# V4_0.net
KiCad netlist of a schematic drawn in Altium Designer
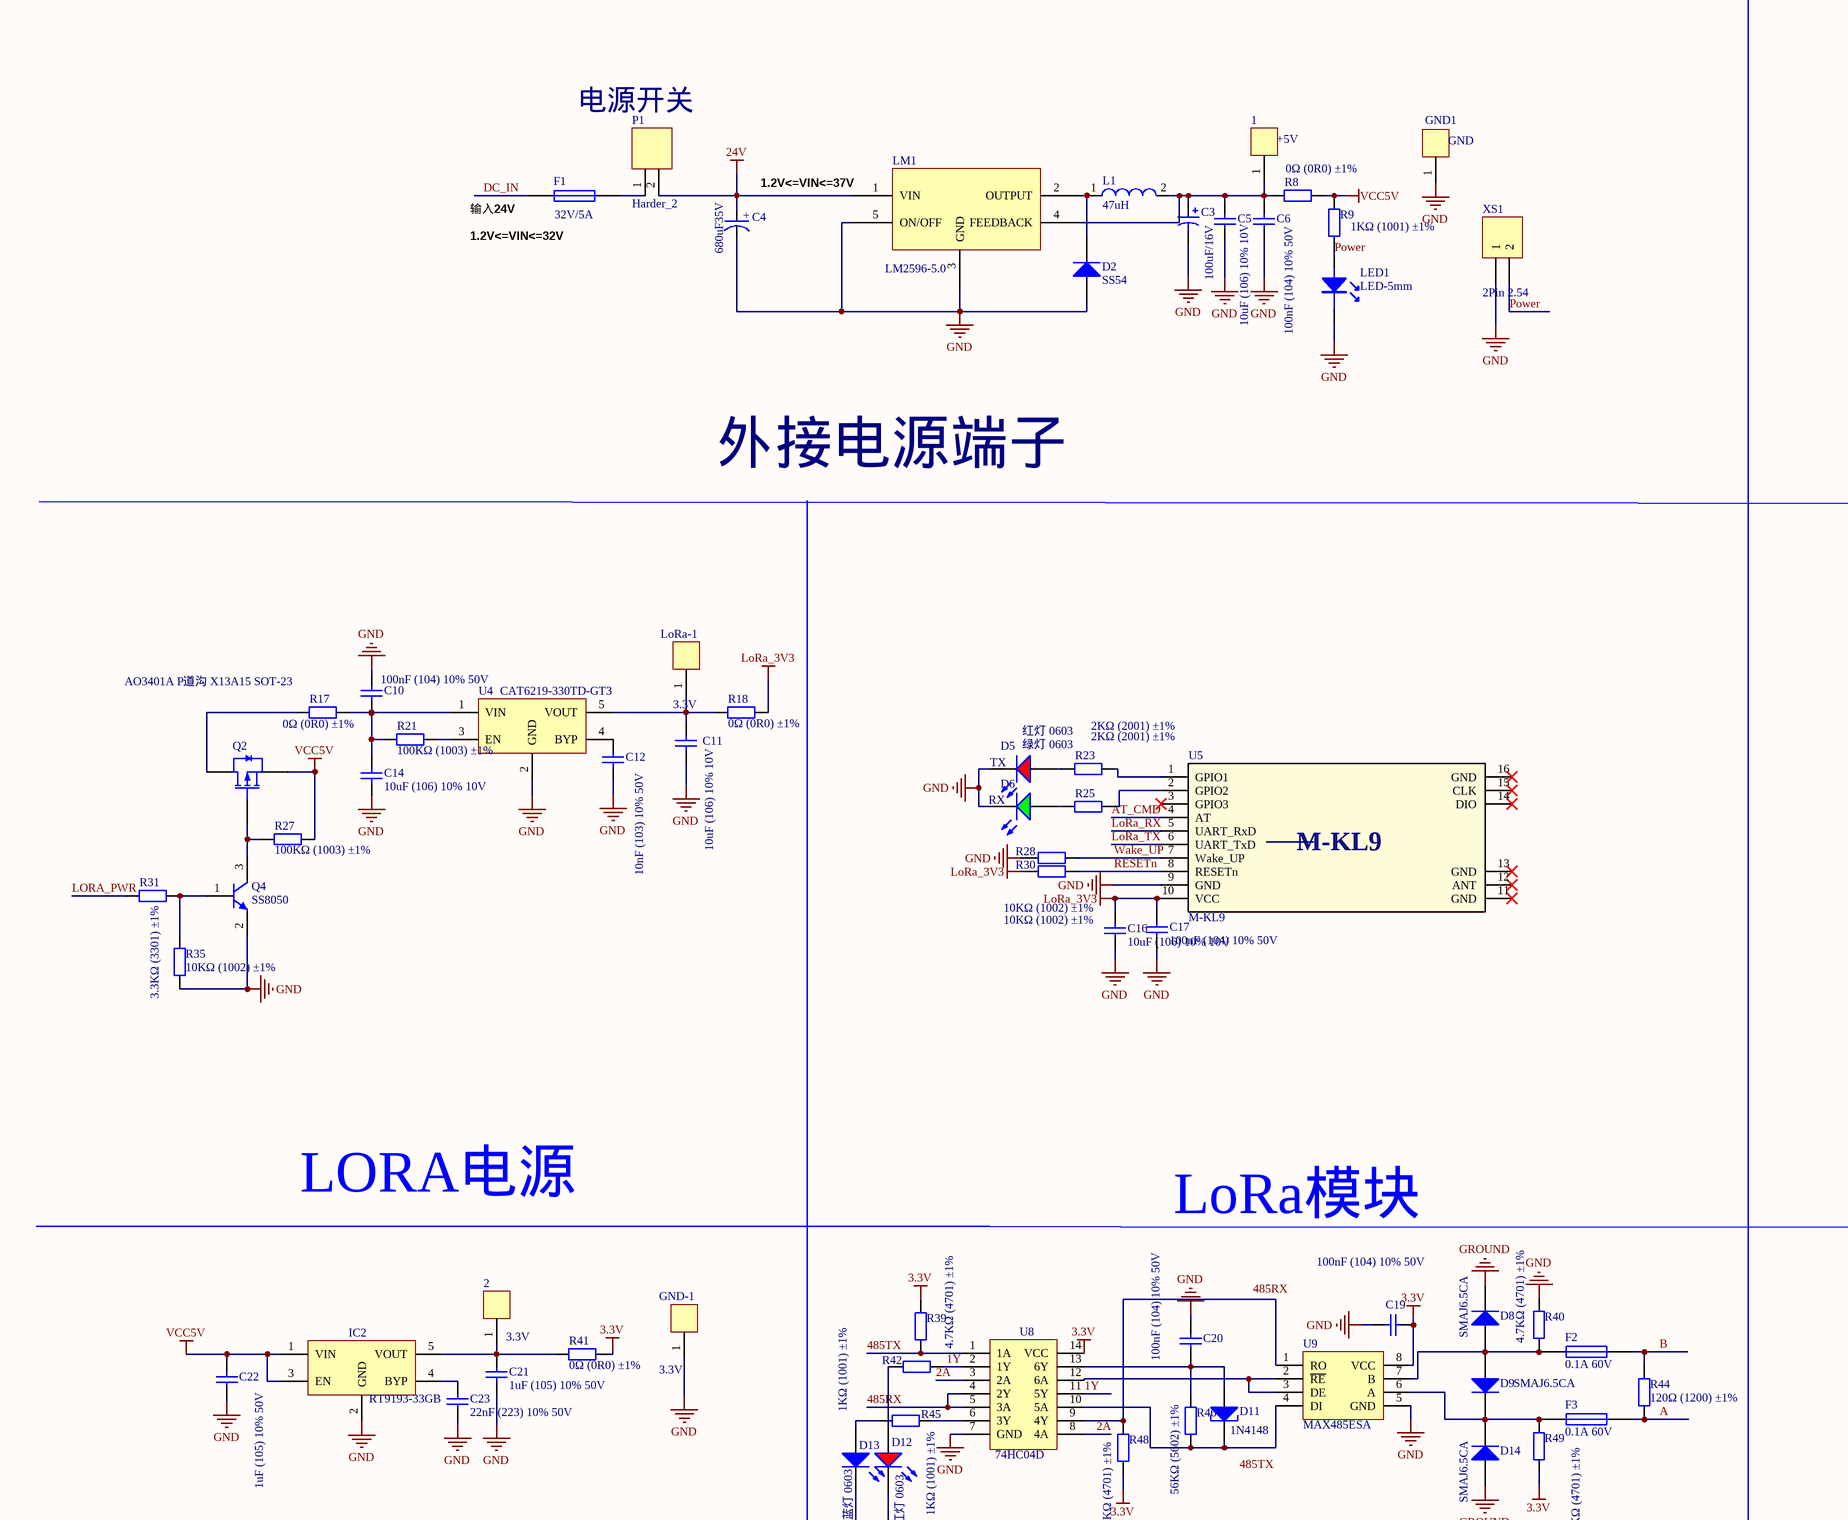
[diagram p0: 电磁阀V4.0.SchDoc, top left]
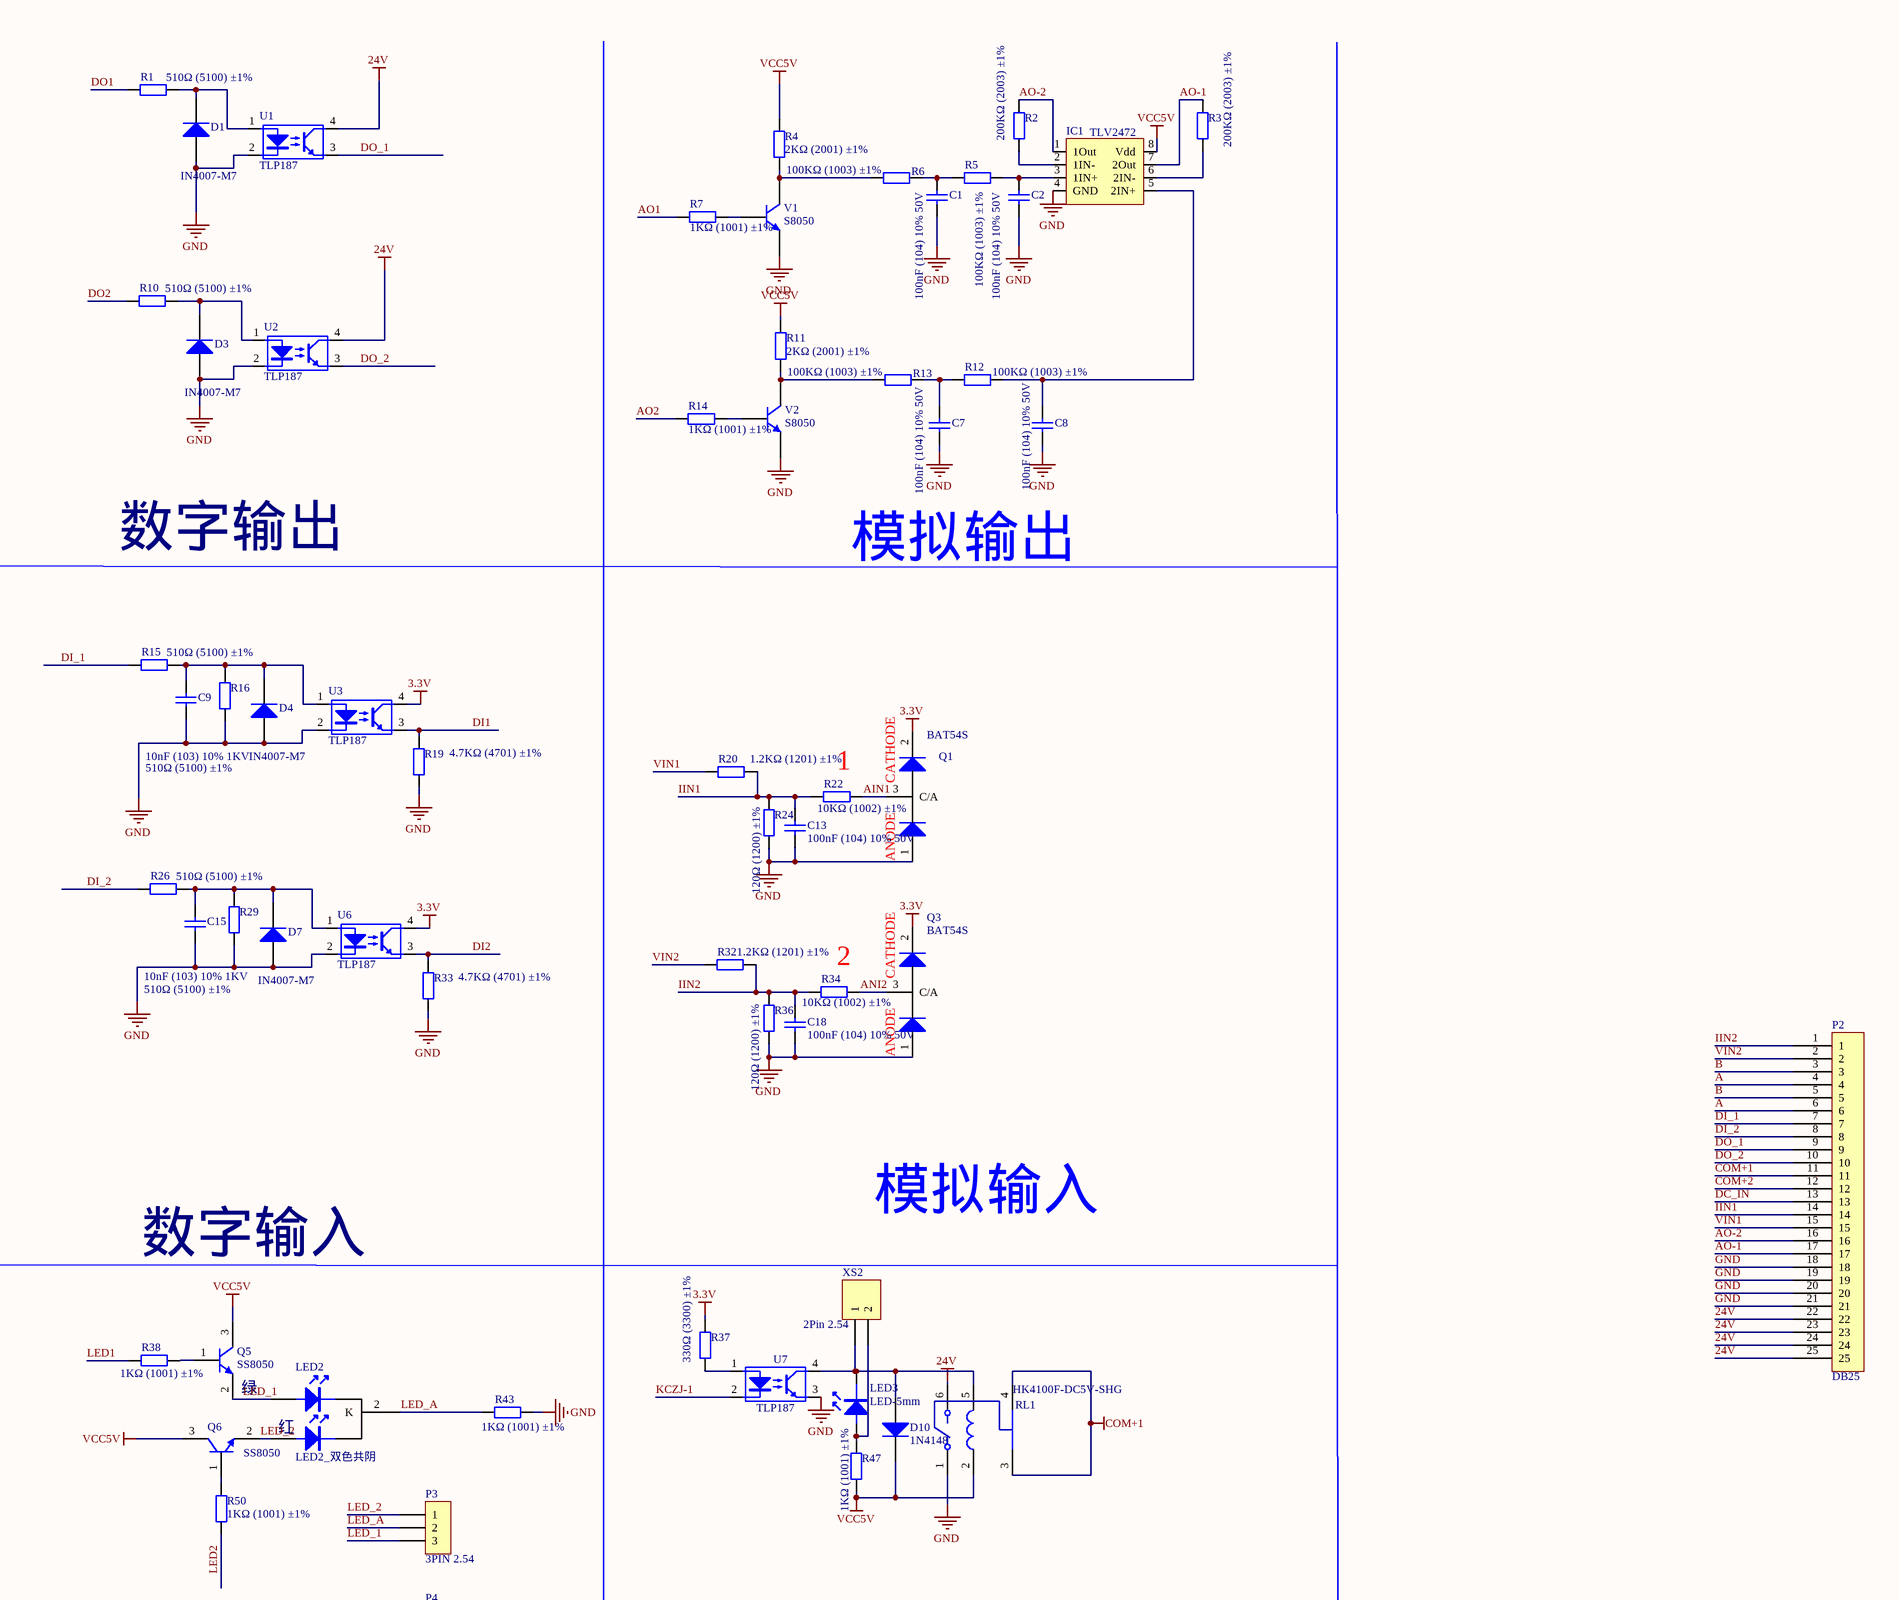
[diagram p1: 电磁阀V4.0.SchDoc, top right]
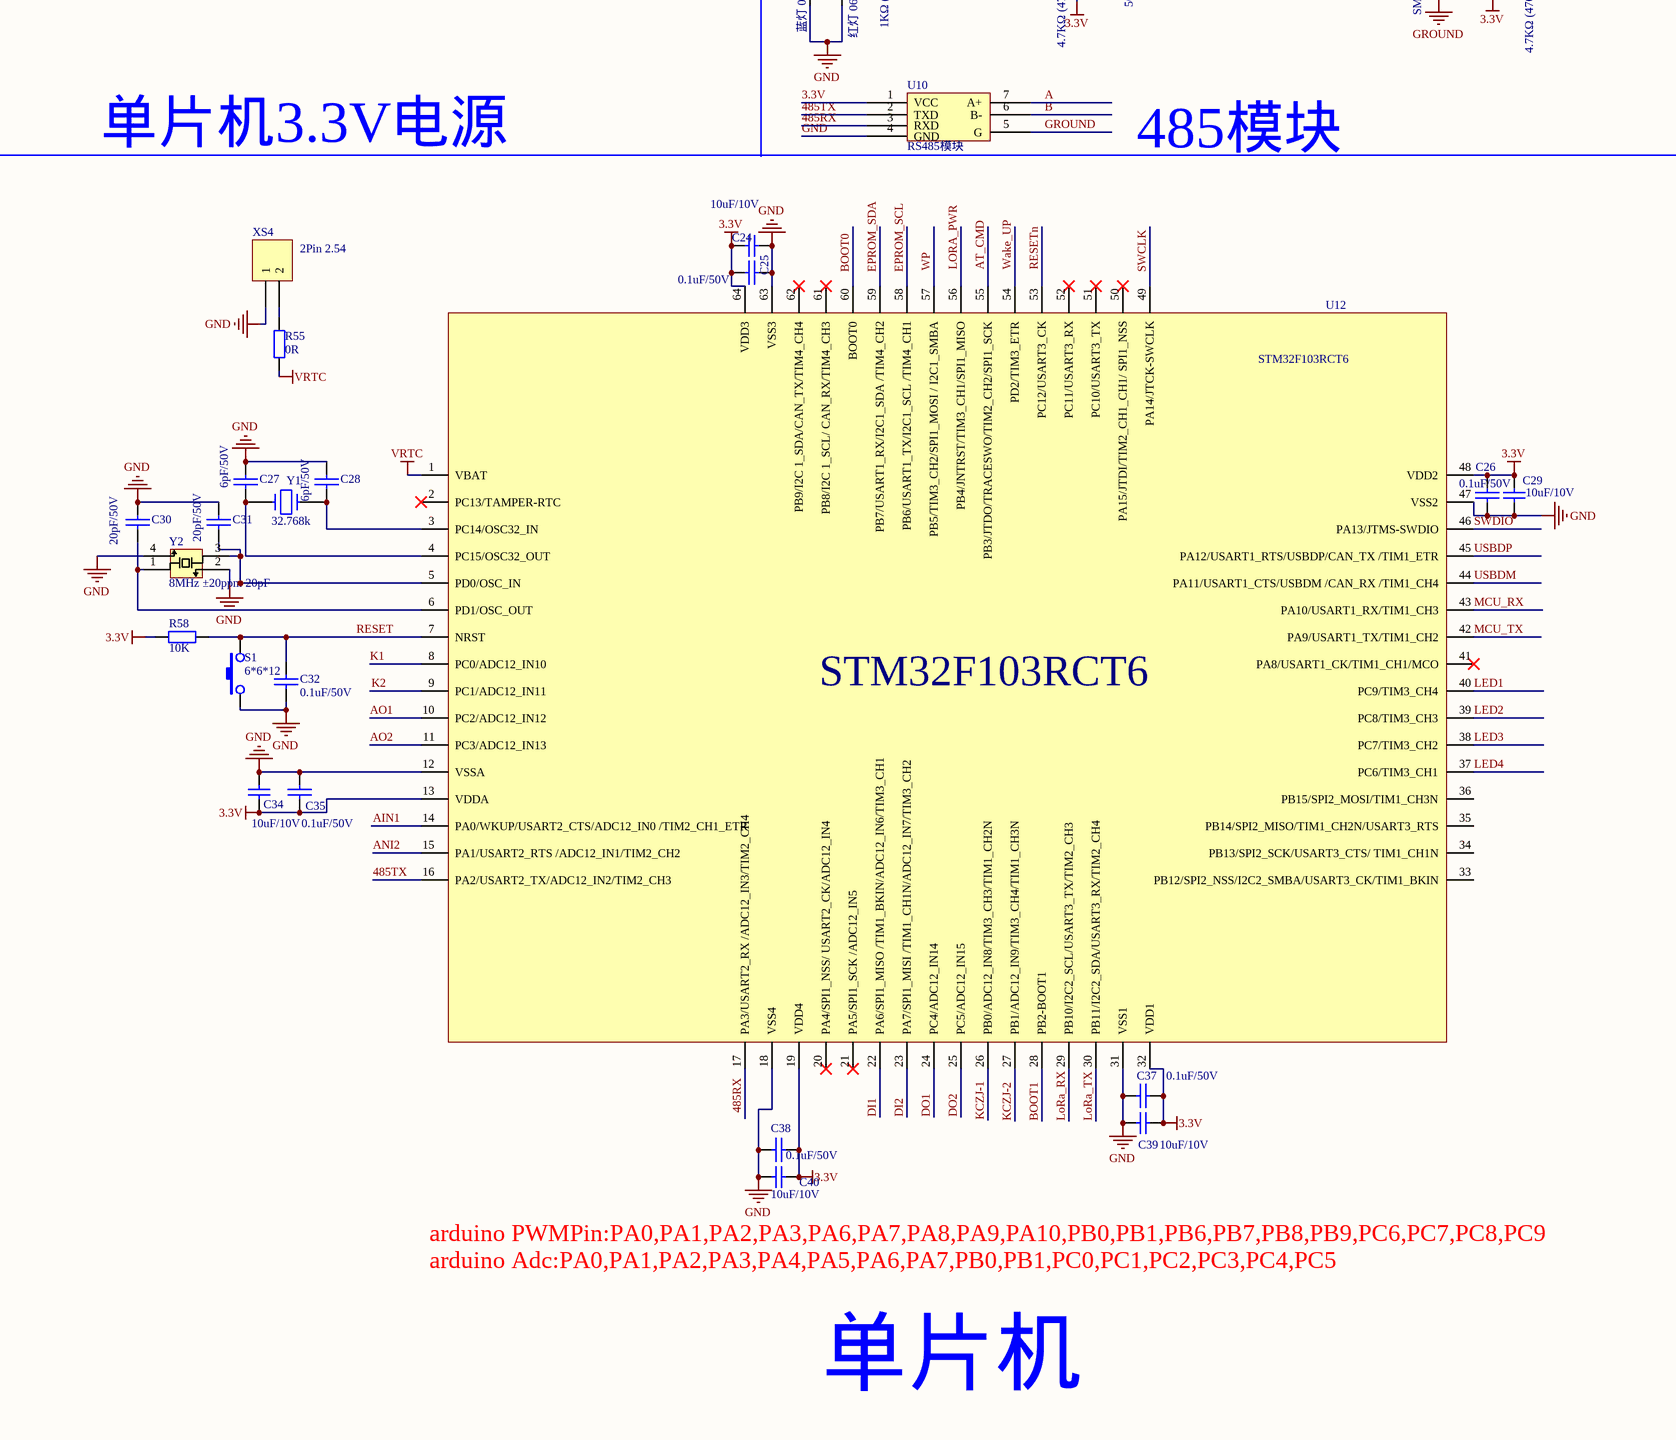
[diagram p2: 电磁阀V4.0.SchDoc, bottom left]
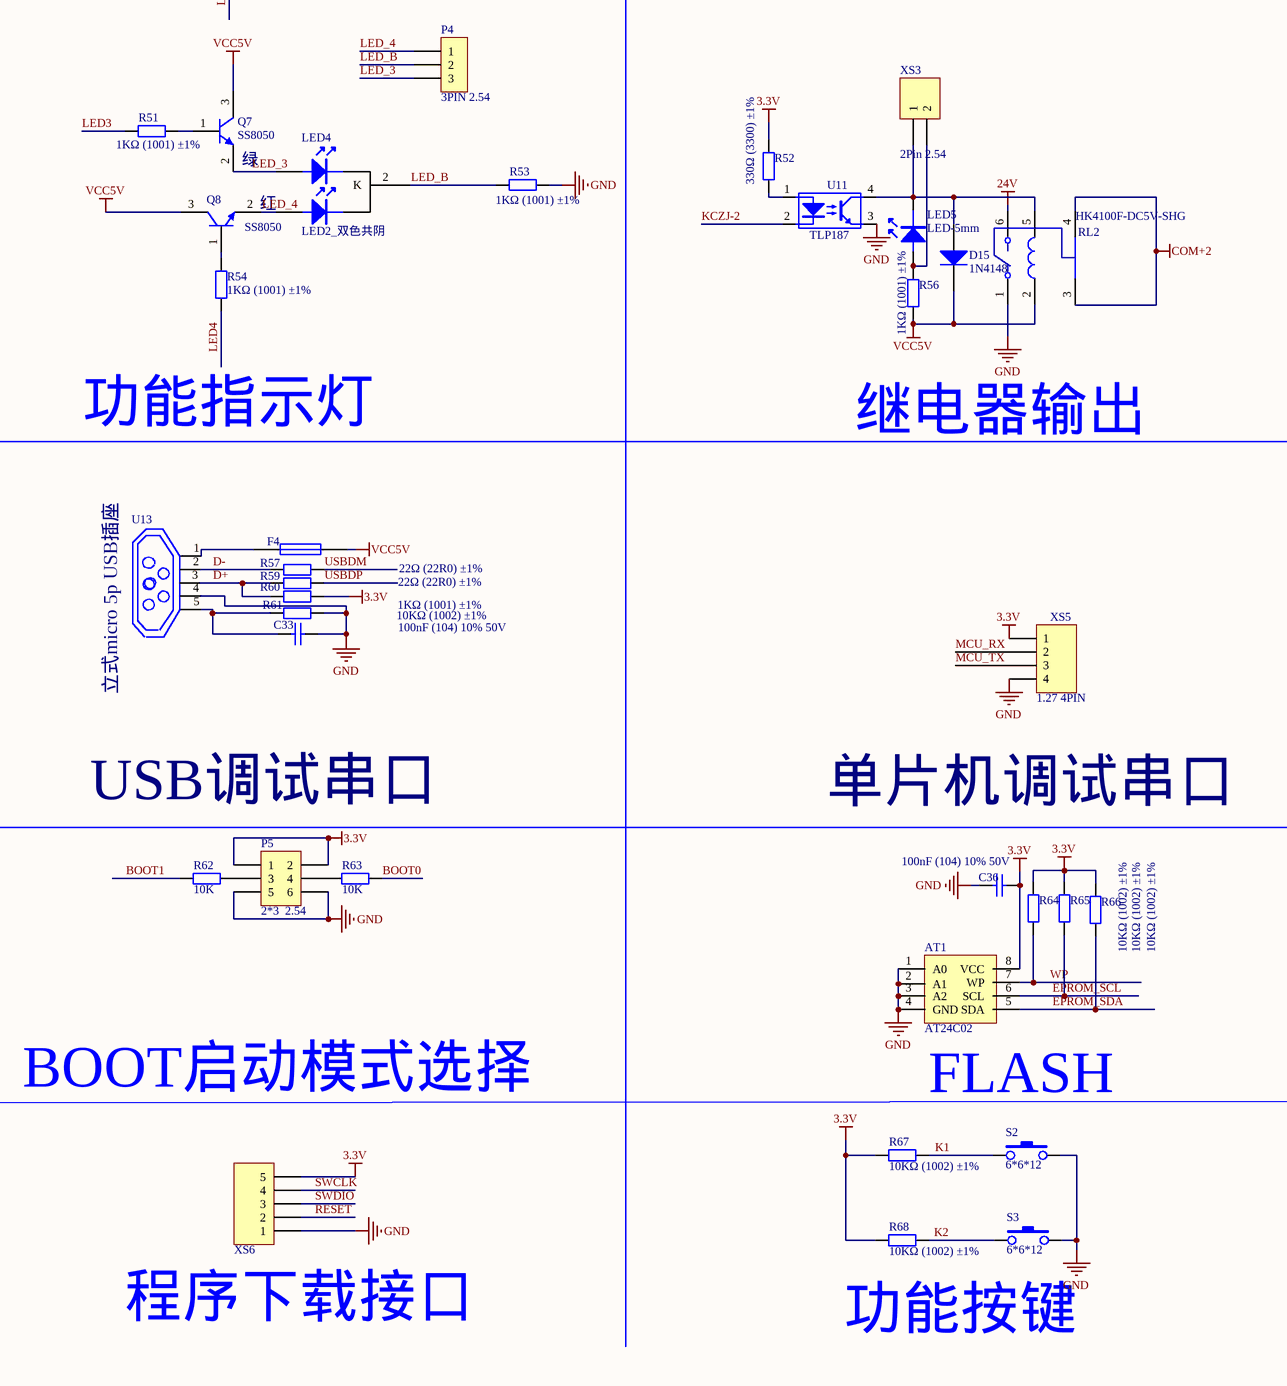
[diagram p3: 电磁阀V4.0.SchDoc, bottom right]

(export (version "E")
  (design (tool "Eeschema 10.0.6"))
  (components
    (comp (ref "1")
      (value "+5V")
      (footprint "TEST_POINT")
      (description "测试点")
      (libsource (lib "InforCenterBoard") (part "TEST_POINT"))
    )
    (comp (ref "2")
      (value "3.3V")
      (footprint "TEST_POINT")
      (description "测试点")
      (libsource (lib "InforCenterBoard") (part "TEST_POINT"))
    )
    (comp (ref "AT1")
      (value "AT24C02")
      (footprint "AT24C02")
      (libsource (lib "AirPlaneSign") (part "AT24C02"))
    )
    (comp (ref "C1")
      (value "100nF (104) 10% 50V")
      (footprint "LC-0603_C")
      (description "贴片电容")
      (libsource (lib "My_Library") (part "0603 100nF (104) 10% 50V"))
    )
    (comp (ref "C2")
      (value "100nF (104) 10% 50V")
      (footprint "LC-0603_C")
      (description "贴片电容")
      (libsource (lib "My_Library") (part "0603 100nF (104) 10% 50V"))
    )
    (comp (ref "C3")
      (value "100uF/16V")
      (footprint "CAP5*X")
      (description "直插电解电容")
      (fields (field (name "PUBLISHER") "Altium Limited"))
      (libsource (lib "kytence") (part "Cap Pol1"))
    )
    (comp (ref "C4") (value "680uF35V") (footprint "C10x16") (libsource (lib "My_Library") (part "CAP_DIP")))
    (comp (ref "C5")
      (value "10uF (106) 10% 10V")
      (footprint "LC-0603_C")
      (description "贴片电容")
      (libsource (lib "My_Library") (part "0603 10uF (106) 10% 10V"))
    )
    (comp (ref "C6")
      (value "100nF (104) 10% 50V")
      (footprint "LC-0603_C")
      (description "贴片电容")
      (libsource (lib "My_Library") (part "0603 100nF (104) 10% 50V"))
    )
    (comp (ref "C7")
      (value "100nF (104) 10% 50V")
      (footprint "LC-0603_C")
      (description "贴片电容")
      (libsource (lib "My_Library") (part "0603 100nF (104) 10% 50V"))
    )
    (comp (ref "C8")
      (value "100nF (104) 10% 50V")
      (footprint "LC-0603_C")
      (description "贴片电容")
      (libsource (lib "My_Library") (part "0603 100nF (104) 10% 50V"))
    )
    (comp (ref "C9")
      (value "10nF (103) 10% 1KV")
      (footprint "LC-1206_C")
      (description "贴片电容")
      (libsource (lib "My_Library") (part "1206 10nF (103) 10% 50V"))
    )
    (comp (ref "C10")
      (value "100nF (104) 10% 50V")
      (footprint "LC-0603_C")
      (description "贴片电容")
      (libsource (lib "My_Library") (part "0603 100nF (104) 10% 50V"))
    )
    (comp (ref "C11")
      (value "10uF (106) 10% 10V")
      (footprint "LC-0603_C")
      (description "贴片电容")
      (libsource (lib "My_Library") (part "0603 10uF (106) 10% 10V"))
    )
    (comp (ref "C12")
      (value "10nF (103) 10% 50V")
      (footprint "LC-0603_C")
      (description "贴片电容")
      (libsource (lib "My_Library") (part "0603 10nF (103) 10% 50V"))
    )
    (comp (ref "C13")
      (value "100nF (104) 10% 50V")
      (footprint "LC-0603_C")
      (description "贴片电容")
      (libsource (lib "My_Library") (part "0603 100nF (104) 10% 50V"))
    )
    (comp (ref "C14")
      (value "10uF (106) 10% 10V")
      (footprint "LC-0603_C")
      (description "贴片电容")
      (libsource (lib "My_Library") (part "0603 10uF (106) 10% 10V"))
    )
    (comp (ref "C15")
      (value "10nF (103) 10% 1KV")
      (footprint "LC-1206_C")
      (description "贴片电容")
      (libsource (lib "My_Library") (part "1206 10nF (103) 10% 50V"))
    )
    (comp (ref "C16")
      (value "10uF (106) 10% 10V")
      (footprint "LC-0603_C")
      (description "贴片电容")
      (libsource (lib "My_Library") (part "0603 10uF (106) 10% 10V"))
    )
    (comp (ref "C17")
      (value "100nF (104) 10% 50V")
      (footprint "LC-0603_C")
      (description "贴片电容")
      (libsource (lib "My_Library") (part "0603 100nF (104) 10% 50V"))
    )
    (comp (ref "C18")
      (value "100nF (104) 10% 50V")
      (footprint "LC-0603_C")
      (description "贴片电容")
      (libsource (lib "My_Library") (part "0603 100nF (104) 10% 50V"))
    )
    (comp (ref "C19")
      (value "100nF (104) 10% 50V")
      (footprint "LC-0603_C")
      (description "贴片电容")
      (libsource (lib "My_Library") (part "0603 100nF (104) 10% 50V"))
    )
    (comp (ref "C20")
      (value "100nF (104) 10% 50V")
      (footprint "LC-0603_C")
      (description "贴片电容")
      (libsource (lib "My_Library") (part "0603 100nF (104) 10% 50V"))
    )
    (comp (ref "C21")
      (value "1uF (105) 10% 50V")
      (footprint "LC-0603_C")
      (description "贴片电容")
      (libsource (lib "My_Library") (part "0603 1uF (105) 10% 50V"))
    )
    (comp (ref "C22")
      (value "1uF (105) 10% 50V")
      (footprint "LC-0603_C")
      (description "贴片电容")
      (libsource (lib "My_Library") (part "0603 1uF (105) 10% 50V"))
    )
    (comp (ref "C23")
      (value "22nF (223) 10% 50V")
      (footprint "LC-0603_C")
      (description "贴片电容")
      (libsource (lib "My_Library") (part "0603 22nF (223) 10% 50V"))
    )
    (comp (ref "C24")
      (value "10uF/10V")
      (footprint "C-0603")
      (description "贴片电容")
      (fields (field (name "PUBLISHER") "Altium Limited"))
      (libsource (lib "Miscellaneous Devices") (part "Cap"))
    )
    (comp (ref "C25")
      (value "0.1uF/50V")
      (footprint "C-0603")
      (description "贴片电容")
      (libsource (lib "*") (part "CAP"))
    )
    (comp (ref "C26")
      (value "0.1uF/50V")
      (footprint "C-0603")
      (description "贴片电容")
      (libsource (lib "*") (part "CAP"))
    )
    (comp (ref "C27")
      (value "6pF/50V")
      (footprint "C-0603")
      (description "贴片电容")
      (libsource (lib "*") (part "CAP"))
    )
    (comp (ref "C28")
      (value "6pF/50V")
      (footprint "C-0603")
      (description "贴片电容")
      (libsource (lib "*") (part "CAP"))
    )
    (comp (ref "C29")
      (value "10uF/10V")
      (footprint "C-0603")
      (description "贴片电容")
      (fields (field (name "PUBLISHER") "Altium Limited"))
      (libsource (lib "Miscellaneous Devices") (part "Cap"))
    )
    (comp (ref "C30")
      (value "20pF/50V")
      (footprint "C-0603")
      (description "贴片电容")
      (libsource (lib "*") (part "CAP"))
    )
    (comp (ref "C31")
      (value "20pF/50V")
      (footprint "C-0603")
      (description "贴片电容")
      (libsource (lib "*") (part "CAP"))
    )
    (comp (ref "C32")
      (value "0.1uF/50V")
      (footprint "C-0603")
      (description "贴片电容")
      (libsource (lib "*") (part "CAP"))
    )
    (comp (ref "C33")
      (value "100nF (104) 10% 50V")
      (footprint "LC-0603_C")
      (description "贴片电容")
      (libsource (lib "My_Library") (part "0603 100nF (104) 10% 50V"))
    )
    (comp (ref "C34")
      (value "10uF/10V")
      (footprint "C-0603")
      (description "贴片电容")
      (fields (field (name "PUBLISHER") "Altium Limited"))
      (libsource (lib "Miscellaneous Devices") (part "Cap"))
    )
    (comp (ref "C35")
      (value "0.1uF/50V")
      (footprint "C-0603")
      (description "贴片电容")
      (libsource (lib "*") (part "CAP"))
    )
    (comp (ref "C36")
      (value "100nF (104) 10% 50V")
      (footprint "LC-0603_C")
      (description "贴片电容")
      (libsource (lib "My_Library") (part "0603 100nF (104) 10% 50V"))
    )
    (comp (ref "C37")
      (value "0.1uF/50V")
      (footprint "C-0603")
      (description "贴片电容")
      (libsource (lib "*") (part "CAP"))
    )
    (comp (ref "C38")
      (value "0.1uF/50V")
      (footprint "C-0603")
      (description "贴片电容")
      (libsource (lib "*") (part "CAP"))
    )
    (comp (ref "C39")
      (value "10uF/10V")
      (footprint "C-0603")
      (description "贴片电容")
      (fields (field (name "PUBLISHER") "Altium Limited"))
      (libsource (lib "Miscellaneous Devices") (part "Cap"))
    )
    (comp (ref "C40")
      (value "10uF/10V")
      (footprint "C-0603")
      (description "贴片电容")
      (fields (field (name "PUBLISHER") "Altium Limited"))
      (libsource (lib "Miscellaneous Devices") (part "Cap"))
    )
    (comp (ref "D1")
      (value "IN4007-M7")
      (footprint "DO-214AC")
      (description "二极管")
      (fields (field (name "PUBLISHER") "Altium Limited"))
      (libsource (lib "Miscellaneous Devices LC") (part "Diode 1N4001"))
    )
    (comp (ref "D2")
      (value "SS54")
      (footprint "LC-SMA(DO-214AC)_S1")
      (description "二极管")
      (libsource (lib "My_Library") (part "SMA(DO-214AC) SS54"))
    )
    (comp (ref "D3")
      (value "IN4007-M7")
      (footprint "DO-214AC")
      (description "二极管")
      (fields (field (name "PUBLISHER") "Altium Limited"))
      (libsource (lib "Miscellaneous Devices LC") (part "Diode 1N4001"))
    )
    (comp (ref "D4")
      (value "IN4007-M7")
      (footprint "DO-214AC")
      (description "二极管")
      (fields (field (name "PUBLISHER") "Altium Limited"))
      (libsource (lib "Miscellaneous Devices LC") (part "Diode 1N4001"))
    )
    (comp (ref "D5")
      (value "红灯 0603")
      (footprint "LC-0603_LED_S1")
      (description "发光二极管")
      (libsource (lib "My_Library") (part "0603 红灯"))
    )
    (comp (ref "D6")
      (value "绿灯 0603")
      (footprint "LC-0603_LED_S1")
      (description "发光二极管")
      (libsource (lib "My_Library") (part "0603 绿灯"))
    )
    (comp (ref "D7")
      (value "IN4007-M7")
      (footprint "DO-214AC")
      (description "二极管")
      (fields (field (name "PUBLISHER") "Altium Limited"))
      (libsource (lib "Miscellaneous Devices LC") (part "Diode 1N4001"))
    )
    (comp (ref "D8")
      (value "SMAJ6.5CA")
      (footprint "DO-214AC")
      (description "通用二极管")
      (fields (field (name "PUBLISHER") "Altium Limited"))
      (libsource (lib "kytence") (part "Diode"))
    )
    (comp (ref "D9")
      (value "SMAJ6.5CA")
      (footprint "DO-214AC")
      (description "通用二极管")
      (fields (field (name "PUBLISHER") "Altium Limited"))
      (libsource (lib "kytence") (part "Diode"))
    )
    (comp (ref "D10")
      (value "1N4148")
      (footprint "SOD-123")
      (description "开关二极管")
      (libsource (lib "SCHEMATIC") (part "开关二极管"))
    )
    (comp (ref "D11")
      (value "1N4148")
      (footprint "LL-34")
      (description "稳压二极管")
      (fields (field (name "PUBLISHER") "Altium Limited"))
      (libsource (lib "Emergency lighting") (part "Diode Zener"))
    )
    (comp (ref "D12")
      (value "红灯 0603")
      (footprint "LC-0603_LED_S1")
      (description "发光二极管")
      (libsource (lib "My_Library") (part "0603 红灯"))
    )
    (comp (ref "D13")
      (value "蓝灯 0603")
      (footprint "LC-0603_LED_S1")
      (description "发光二极管")
      (libsource (lib "My_Library") (part "0603 蓝灯"))
    )
    (comp (ref "D14")
      (value "SMAJ6.5CA")
      (footprint "DO-214AC")
      (description "通用二极管")
      (fields (field (name "PUBLISHER") "Altium Limited"))
      (libsource (lib "kytence") (part "Diode"))
    )
    (comp (ref "D15")
      (value "1N4148")
      (footprint "SOD-123")
      (description "开关二极管")
      (libsource (lib "SCHEMATIC") (part "开关二极管"))
    )
    (comp (ref "F1")
      (value "32V/5A")
      (footprint "Fuse-1206")
      (description "贴片保险丝")
      (fields (field (name "PUBLISHER") "Altium Limited"))
      (libsource (lib "Emergency lighting") (part "Fuse"))
    )
    (comp (ref "F2")
      (value "0.1A 60V")
      (footprint "R-1812")
      (description "贴片保险丝 0.1A 60V")
      (fields (field (name "PUBLISHER") "Altium Limited"))
      (libsource (lib "AirPlaneSign") (part "Fuse_1"))
    )
    (comp (ref "F3")
      (value "0.1A 60V")
      (footprint "R-1812")
      (description "贴片保险丝 0.1A 60V")
      (fields (field (name "PUBLISHER") "Altium Limited"))
      (libsource (lib "AirPlaneSign") (part "Fuse_1"))
    )
    (comp (ref "F4")
      (value "32V/5A")
      (footprint "FUSE-1206")
      (description "贴片保险丝")
      (fields (field (name "PUBLISHER") "Altium Limited"))
      (libsource (lib "AirPlaneSign") (part "Fuse"))
    )
    (comp (ref "GND-1")
      (value "3.3V")
      (footprint "TEST_POINT")
      (description "测试点")
      (libsource (lib "InforCenterBoard") (part "TEST_POINT"))
    )
    (comp (ref "GND1")
      (value "GND")
      (footprint "TEST_POINT")
      (description "测试点")
      (libsource (lib "InforCenterBoard") (part "TEST_POINT"))
    )
    (comp (ref "IC1")
      (value "TLV2472")
      (footprint "SOP8")
      (description "输出放大")
      (libsource (lib "Arduino-PLC") (part "TLV2472"))
    )
    (comp (ref "IC2")
      (value "RT9193-33GB")
      (footprint "SOT23-5")
      (description "低压差线性稳压(LDO)")
      (libsource (lib "FM") (part "CAT6219"))
    )
    (comp (ref "L1")
      (value "47uH")
      (footprint "SMD,13.8x12.6x7mm")
      (description "4R7功率电感")
      (fields (field (name "Comment") "47uH ±20%") (field (name "PUBLISHER") "Altium Limited"))
      (libsource (lib "AirPlaneSign") (part "47uH ±20%"))
    )
    (comp (ref "LED1")
      (value "LED-5mm")
      (footprint "LED_5mm")
      (description "发光二极管")
      (libsource (lib "AirPlaneSign") (part "LED-5mm"))
    )
    (comp (ref "LED2")
      (value "LED2_双色共阴")
      (footprint "双色LED")
      (libsource (lib "AirPlaneSign") (part "LED2_双色共阴"))
    )
    (comp (ref "LED3")
      (value "LED-5mm")
      (footprint "LED_5mm")
      (description "发光二极管")
      (libsource (lib "AirPlaneSign") (part "LED-5mm"))
    )
    (comp (ref "LED4")
      (value "LED2_双色共阴")
      (footprint "双色LED")
      (libsource (lib "AirPlaneSign") (part "LED2_双色共阴"))
    )
    (comp (ref "LED5")
      (value "LED-5mm")
      (footprint "LED_5mm")
      (description "发光二极管")
      (libsource (lib "AirPlaneSign") (part "LED-5mm"))
    )
    (comp (ref "LM1") (value "LM2596-5.0") (footprint "LC-TO-263-5") (libsource (lib "LZH") (part "LM2596")))
    (comp (ref "LoRa-1")
      (value "3.3V")
      (footprint "TEST_POINT")
      (description "测试点")
      (libsource (lib "InforCenterBoard") (part "TEST_POINT"))
    )
    (comp (ref "P1")
      (value "Harder_2")
      (footprint "2Pin-2.54A")
      (libsource (lib "My_Library") (part "Harder_2"))
    )
    (comp (ref "P2")
      (value "DB25")
      (footprint "DB25")
      (description "DR25弯针")
      (libsource (lib "AirPlaneSign") (part "DB25"))
    )
    (comp (ref "P3")
      (value "3PIN 2.54")
      (footprint "JXT-3-l")
      (description "单排插针")
      (fields (field (name "PUBLISHER") "Altium Limited"))
      (libsource (lib "AirPlaneSign") (part "Header 3H"))
    )
    (comp (ref "P4")
      (value "3PIN 2.54")
      (footprint "JXT-3-l")
      (description "单排插针")
      (fields (field (name "PUBLISHER") "Altium Limited"))
      (libsource (lib "AirPlaneSign") (part "Header 3H"))
    )
    (comp (ref "P5")
      (value "2*3  2.54")
      (footprint "201S2X3")
      (description "双排插针")
      (fields (field (name "PUBLISHER") "Altium Limited"))
      (libsource (lib "AirPlaneSign") (part "Header 2*3"))
    )
    (comp (ref "Q1")
      (value "BAT54S")
      (footprint "SOT-23-3")
      (description "肖特基二极管")
      (libsource (lib "AirPlaneSign") (part "BAT54S"))
    )
    (comp (ref "Q2")
      (value "AO3401A P道沟 X13A15 SOT-23")
      (footprint "LC-SOT-23-3L")
      (description "MOS(场效应管)")
      (libsource (lib "My_Library") (part "AO3401A P道沟 X13A15 SOT-23"))
    )
    (comp (ref "Q3")
      (value "BAT54S")
      (footprint "SOT-23-3")
      (description "肖特基二极管")
      (libsource (lib "AirPlaneSign") (part "BAT54S"))
    )
    (comp (ref "Q4")
      (value "SS8050")
      (footprint "SOT-23")
      (description "NPN贴片三极管")
      (fields (field (name "PUBLISHER") "Altium Limited"))
      (libsource (lib "My_Library") (part "SS8050"))
    )
    (comp (ref "Q5")
      (value "SS8050")
      (footprint "SOT-23")
      (description "NPN贴片三极管")
      (fields (field (name "PUBLISHER") "Altium Limited"))
      (libsource (lib "My_Library") (part "SS8050"))
    )
    (comp (ref "Q6")
      (value "SS8050")
      (footprint "SOT-23")
      (description "NPN贴片三极管")
      (fields (field (name "PUBLISHER") "Altium Limited"))
      (libsource (lib "My_Library") (part "SS8050"))
    )
    (comp (ref "Q7")
      (value "SS8050")
      (footprint "SOT-23")
      (description "NPN贴片三极管")
      (fields (field (name "PUBLISHER") "Altium Limited"))
      (libsource (lib "My_Library") (part "SS8050"))
    )
    (comp (ref "Q8")
      (value "SS8050")
      (footprint "SOT-23")
      (description "NPN贴片三极管")
      (fields (field (name "PUBLISHER") "Altium Limited"))
      (libsource (lib "My_Library") (part "SS8050"))
    )
    (comp (ref "R1")
      (value "510Ω (5100) ±1%")
      (footprint "LC-0603_R")
      (description "贴片电阻")
      (libsource (lib "") (part "0603 510Ω (5100) 1%_1"))
    )
    (comp (ref "R2")
      (value "200KΩ (2003) ±1%")
      (footprint "LC-0603_R")
      (description "贴片电阻")
      (libsource (lib "My_Library") (part "0603 200KΩ (2003) 1%"))
    )
    (comp (ref "R3")
      (value "200KΩ (2003) ±1%")
      (footprint "LC-0603_R")
      (description "贴片电阻")
      (libsource (lib "My_Library") (part "0603 200KΩ (2003) 1%"))
    )
    (comp (ref "R4")
      (value "2KΩ (2001) ±1%")
      (footprint "LC-0603_R")
      (description "贴片电阻")
      (libsource (lib "") (part "0603 2KΩ (2001) 1%_1"))
    )
    (comp (ref "R5")
      (value "100KΩ (1003) ±1%")
      (footprint "LC-0603_R")
      (description "贴片电阻")
      (libsource (lib "My_Library") (part "0603 100KΩ (1003) 1%"))
    )
    (comp (ref "R6")
      (value "100KΩ (1003) ±1%")
      (footprint "LC-0603_R")
      (description "贴片电阻")
      (libsource (lib "My_Library") (part "0603 100KΩ (1003) 1%"))
    )
    (comp (ref "R7")
      (value "1KΩ (1001) ±1%")
      (footprint "LC-0603_R")
      (description "贴片电阻")
      (libsource (lib "") (part "0603 1KΩ (1001) 1%_2"))
    )
    (comp (ref "R8")
      (value "0Ω (0R0) ±1%")
      (footprint "LC-0603_R")
      (description "贴片电阻")
      (libsource (lib "My_Library") (part "0603 0Ω (0R0) 1%"))
    )
    (comp (ref "R9")
      (value "1KΩ (1001) ±1%")
      (footprint "LC-0603_R")
      (description "贴片电阻")
      (libsource (lib "") (part "0603 1KΩ (1001) 1%_1"))
    )
    (comp (ref "R10")
      (value "510Ω (5100) ±1%")
      (footprint "LC-0603_R")
      (description "贴片电阻")
      (libsource (lib "") (part "0603 510Ω (5100) 1%_1"))
    )
    (comp (ref "R11")
      (value "2KΩ (2001) ±1%")
      (footprint "LC-0603_R")
      (description "贴片电阻")
      (libsource (lib "") (part "0603 2KΩ (2001) 1%_1"))
    )
    (comp (ref "R12")
      (value "100KΩ (1003) ±1%")
      (footprint "LC-0603_R")
      (description "贴片电阻")
      (libsource (lib "My_Library") (part "0603 100KΩ (1003) 1%"))
    )
    (comp (ref "R13")
      (value "100KΩ (1003) ±1%")
      (footprint "LC-0603_R")
      (description "贴片电阻")
      (libsource (lib "My_Library") (part "0603 100KΩ (1003) 1%"))
    )
    (comp (ref "R14")
      (value "1KΩ (1001) ±1%")
      (footprint "LC-0603_R")
      (description "贴片电阻")
      (libsource (lib "") (part "0603 1KΩ (1001) 1%_2"))
    )
    (comp (ref "R15")
      (value "510Ω (5100) ±1%")
      (footprint "LC-0603_R")
      (description "贴片电阻")
      (libsource (lib "") (part "0603 510Ω (5100) 1%_1"))
    )
    (comp (ref "R16")
      (value "510Ω (5100) ±1%")
      (footprint "LC-0603_R")
      (description "贴片电阻")
      (libsource (lib "My_Library") (part "0603 510Ω (5100) 1%"))
    )
    (comp (ref "R17")
      (value "0Ω (0R0) ±1%")
      (footprint "LC-0603_R")
      (description "贴片电阻")
      (libsource (lib "My_Library") (part "0603 0Ω (0R0) 1%"))
    )
    (comp (ref "R18")
      (value "0Ω (0R0) ±1%")
      (footprint "LC-0603_R")
      (description "贴片电阻")
      (libsource (lib "My_Library") (part "0603 0Ω (0R0) 1%"))
    )
    (comp (ref "R19")
      (value "4.7KΩ (4701) ±1%")
      (footprint "LC-0603_R")
      (description "贴片电阻")
      (libsource (lib "My_Library") (part "0603 4.7KΩ (4701) 1%"))
    )
    (comp (ref "R20")
      (value "1.2KΩ (1201) ±1%")
      (footprint "LC-0603_R")
      (description "贴片电阻")
      (libsource (lib "My_Library") (part "0603 1.2KΩ (1201) 1%"))
    )
    (comp (ref "R21")
      (value "100KΩ (1003) ±1%")
      (footprint "LC-0603_R")
      (description "贴片电阻")
      (libsource (lib "My_Library") (part "0603 100KΩ (1003) 1%"))
    )
    (comp (ref "R22")
      (value "10KΩ (1002) ±1%")
      (footprint "LC-0603_R")
      (description "贴片电阻")
      (libsource (lib "") (part "0603 10KΩ (1002) 1%_1"))
    )
    (comp (ref "R23")
      (value "2KΩ (2001) ±1%")
      (footprint "LC-0603_R")
      (description "贴片电阻")
      (libsource (lib "My_Library") (part "0603 2KΩ (2001) 1%"))
    )
    (comp (ref "R24")
      (value "120Ω (1200) ±1%")
      (footprint "LC-0603_R")
      (description "贴片电阻")
      (libsource (lib "My_Library") (part "0603 120Ω (1200) 1%"))
    )
    (comp (ref "R25")
      (value "2KΩ (2001) ±1%")
      (footprint "LC-0603_R")
      (description "贴片电阻")
      (libsource (lib "My_Library") (part "0603 2KΩ (2001) 1%"))
    )
    (comp (ref "R26")
      (value "510Ω (5100) ±1%")
      (footprint "LC-0603_R")
      (description "贴片电阻")
      (libsource (lib "") (part "0603 510Ω (5100) 1%_1"))
    )
    (comp (ref "R27")
      (value "100KΩ (1003) ±1%")
      (footprint "LC-0603_R")
      (description "贴片电阻")
      (libsource (lib "E32-TTL_LoRa_SENSOR-V3.0") (part "0603 100KΩ (1003) 1%"))
    )
    (comp (ref "R28")
      (value "10KΩ (1002) ±1%")
      (footprint "LC-0603_R")
      (description "贴片电阻")
      (libsource (lib "") (part "0603 10KΩ (1002) 1%_1"))
    )
    (comp (ref "R29")
      (value "510Ω (5100) ±1%")
      (footprint "LC-0603_R")
      (description "贴片电阻")
      (libsource (lib "My_Library") (part "0603 510Ω (5100) 1%"))
    )
    (comp (ref "R30")
      (value "10KΩ (1002) ±1%")
      (footprint "LC-0603_R")
      (description "贴片电阻")
      (libsource (lib "") (part "0603 10KΩ (1002) 1%_1"))
    )
    (comp (ref "R31")
      (value "3.3KΩ (3301) ±1%")
      (footprint "LC-0603_R")
      (description "贴片电阻")
      (libsource (lib "My_Library") (part "0603 3.3KΩ (3301) 1%"))
    )
    (comp (ref "R32")
      (value "1.2KΩ (1201) ±1%")
      (footprint "LC-0603_R")
      (description "贴片电阻")
      (libsource (lib "My_Library") (part "0603 1.2KΩ (1201) 1%"))
    )
    (comp (ref "R33")
      (value "4.7KΩ (4701) ±1%")
      (footprint "LC-0603_R")
      (description "贴片电阻")
      (libsource (lib "My_Library") (part "0603 4.7KΩ (4701) 1%"))
    )
    (comp (ref "R34")
      (value "10KΩ (1002) ±1%")
      (footprint "LC-0603_R")
      (description "贴片电阻")
      (libsource (lib "") (part "0603 10KΩ (1002) 1%_1"))
    )
    (comp (ref "R35")
      (value "10KΩ (1002) ±1%")
      (footprint "LC-0603_R")
      (description "贴片电阻")
      (libsource (lib "") (part "0603 10KΩ (1002) 1%_2"))
    )
    (comp (ref "R36")
      (value "120Ω (1200) ±1%")
      (footprint "LC-0603_R")
      (description "贴片电阻")
      (libsource (lib "My_Library") (part "0603 120Ω (1200) 1%"))
    )
    (comp (ref "R37")
      (value "330Ω (3300) ±1%")
      (footprint "LC-0603_R")
      (description "贴片电阻")
      (libsource (lib "My_Library") (part "0603 330Ω (3300) 1%"))
    )
    (comp (ref "R38")
      (value "1KΩ (1001) ±1%")
      (footprint "LC-0603_R")
      (description "贴片电阻")
      (libsource (lib "") (part "0603 1KΩ (1001) 1%_2"))
    )
    (comp (ref "R39")
      (value "4.7KΩ (4701) ±1%")
      (footprint "LC-0603_R")
      (description "贴片电阻")
      (libsource (lib "My_Library") (part "0603 4.7KΩ (4701) 1%"))
    )
    (comp (ref "R40")
      (value "4.7KΩ (4701) ±1%")
      (footprint "LC-0603_R")
      (description "贴片电阻")
      (libsource (lib "") (part "0603 4.7KΩ (4701) 1%_1"))
    )
    (comp (ref "R41")
      (value "0Ω (0R0) ±1%")
      (footprint "LC-0603_R")
      (description "贴片电阻")
      (libsource (lib "My_Library") (part "0603 0Ω (0R0) 1%"))
    )
    (comp (ref "R42")
      (value "1KΩ (1001) ±1%")
      (footprint "LC-0603_R")
      (description "贴片电阻")
      (libsource (lib "") (part "0603 1KΩ (1001) 1%_2"))
    )
    (comp (ref "R43")
      (value "1KΩ (1001) ±1%")
      (footprint "LC-0603_R")
      (description "贴片电阻")
      (libsource (lib "") (part "0603 1KΩ (1001) 1%_3"))
    )
    (comp (ref "R44")
      (value "120Ω (1200) ±1%")
      (footprint "LC-0603_R")
      (description "贴片电阻")
      (libsource (lib "My_Library") (part "0603 120Ω (1200) 1%"))
    )
    (comp (ref "R45")
      (value "1KΩ (1001) ±1%")
      (footprint "LC-0603_R")
      (description "贴片电阻")
      (libsource (lib "") (part "0603 1KΩ (1001) 1%_2"))
    )
    (comp (ref "R46")
      (value "56KΩ (5602) ±1%")
      (footprint "LC-0603_R")
      (description "贴片电阻")
      (libsource (lib "My_Library") (part "0603 56KΩ (5602) 1%"))
    )
    (comp (ref "R47")
      (value "1KΩ (1001) ±1%")
      (footprint "LC-0603_R")
      (description "贴片电阻")
      (libsource (lib "My_Library") (part "0603 1KΩ (1001) 1%"))
    )
    (comp (ref "R48")
      (value "4.7KΩ (4701) ±1%")
      (footprint "LC-0603_R")
      (description "贴片电阻")
      (libsource (lib "My_Library") (part "0603 4.7KΩ (4701) 1%"))
    )
    (comp (ref "R49")
      (value "4.7KΩ (4701) ±1%")
      (footprint "LC-0603_R")
      (description "贴片电阻")
      (libsource (lib "My_Library") (part "0603 4.7KΩ (4701) 1%"))
    )
    (comp (ref "R50")
      (value "1KΩ (1001) ±1%")
      (footprint "LC-0603_R")
      (description "贴片电阻")
      (libsource (lib "") (part "0603 1KΩ (1001) 1%_1"))
    )
    (comp (ref "R51")
      (value "1KΩ (1001) ±1%")
      (footprint "LC-0603_R")
      (description "贴片电阻")
      (libsource (lib "") (part "0603 1KΩ (1001) 1%_2"))
    )
    (comp (ref "R52")
      (value "330Ω (3300) ±1%")
      (footprint "LC-0603_R")
      (description "贴片电阻")
      (libsource (lib "My_Library") (part "0603 330Ω (3300) 1%"))
    )
    (comp (ref "R53")
      (value "1KΩ (1001) ±1%")
      (footprint "LC-0603_R")
      (description "贴片电阻")
      (libsource (lib "") (part "0603 1KΩ (1001) 1%_3"))
    )
    (comp (ref "R54")
      (value "1KΩ (1001) ±1%")
      (footprint "LC-0603_R")
      (description "贴片电阻")
      (libsource (lib "") (part "0603 1KΩ (1001) 1%_1"))
    )
    (comp (ref "R55")
      (value "0R")
      (footprint "R-0603")
      (description "贴片电阻")
      (fields (field (name "PUBLISHER") "Altium Limited"))
      (libsource (lib "Miscellaneous Devices") (part "Res2"))
    )
    (comp (ref "R56")
      (value "1KΩ (1001) ±1%")
      (footprint "LC-0603_R")
      (description "贴片电阻")
      (libsource (lib "My_Library") (part "0603 1KΩ (1001) 1%"))
    )
    (comp (ref "R57")
      (value "22Ω (22R0) ±1%")
      (footprint "LC-0603_R")
      (description "贴片电阻")
      (libsource (lib "My_Library") (part "0603 22Ω (22R0) 1%"))
    )
    (comp (ref "R58")
      (value "10K")
      (footprint "R-0603")
      (description "贴片电阻")
      (fields (field (name "PUBLISHER") "Altium Limited"))
      (libsource (lib "") (part "Res2_1"))
    )
    (comp (ref "R59")
      (value "22Ω (22R0) ±1%")
      (footprint "LC-0603_R")
      (description "贴片电阻")
      (libsource (lib "My_Library") (part "0603 22Ω (22R0) 1%"))
    )
    (comp (ref "R60")
      (value "1KΩ (1001) ±1%")
      (footprint "LC-0603_R")
      (description "贴片电阻")
      (libsource (lib "") (part "0603 1KΩ (1001) 1%_2"))
    )
    (comp (ref "R61")
      (value "10KΩ (1002) ±1%")
      (footprint "LC-0603_R")
      (description "贴片电阻")
      (libsource (lib "My_Library") (part "0603 10KΩ (1002) 1%"))
    )
    (comp (ref "R62")
      (value "10K")
      (footprint "R-0603")
      (description "贴片电阻")
      (fields (field (name "PUBLISHER") "Altium Limited"))
      (libsource (lib "") (part "Res2_2"))
    )
    (comp (ref "R63")
      (value "10K")
      (footprint "R-0603")
      (description "贴片电阻")
      (fields (field (name "PUBLISHER") "Altium Limited"))
      (libsource (lib "") (part "Res2_2"))
    )
    (comp (ref "R64")
      (value "10KΩ (1002) ±1%")
      (footprint "LC-0603_R")
      (description "贴片电阻")
      (libsource (lib "") (part "0603 10KΩ (1002) 1%_2"))
    )
    (comp (ref "R65")
      (value "10KΩ (1002) ±1%")
      (footprint "LC-0603_R")
      (description "贴片电阻")
      (libsource (lib "") (part "0603 10KΩ (1002) 1%_2"))
    )
    (comp (ref "R66")
      (value "10KΩ (1002) ±1%")
      (footprint "LC-0603_R")
      (description "贴片电阻")
      (libsource (lib "") (part "0603 10KΩ (1002) 1%_2"))
    )
    (comp (ref "R67")
      (value "10KΩ (1002) ±1%")
      (footprint "LC-0603_R")
      (description "贴片电阻")
      (libsource (lib "") (part "0603 10KΩ (1002) 1%_1"))
    )
    (comp (ref "R68")
      (value "10KΩ (1002) ±1%")
      (footprint "LC-0603_R")
      (description "贴片电阻")
      (libsource (lib "") (part "0603 10KΩ (1002) 1%_1"))
    )
    (comp (ref "RL1")
      (value "HK4100F-DC5V-SHG")
      (footprint "HK4100F-DC5V-SHG")
      (description "继电器")
      (fields (field (name "PUBLISHER") "Altium Limited"))
      (libsource (lib "AirPlaneSign") (part "HK4100F-DC5V-SHG"))
    )
    (comp (ref "RL2")
      (value "HK4100F-DC5V-SHG")
      (footprint "HK4100F-DC5V-SHG")
      (description "继电器")
      (fields (field (name "PUBLISHER") "Altium Limited"))
      (libsource (lib "AirPlaneSign") (part "HK4100F-DC5V-SHG"))
    )
    (comp (ref "S1")
      (value "6*6*12")
      (footprint "KEY-7.0*7.0")
      (description "侧脚带支架 微型按键")
      (libsource (lib "AirPlaneSign") (part "SW-PB_4"))
    )
    (comp (ref "S2")
      (value "6*6*12")
      (footprint "KEY-7.0*7.0")
      (description "侧脚带支架 微型按键")
      (libsource (lib "AirPlaneSign") (part "SW-PB_4"))
    )
    (comp (ref "S3")
      (value "6*6*12")
      (footprint "KEY-7.0*7.0")
      (description "侧脚带支架 微型按键")
      (libsource (lib "AirPlaneSign") (part "SW-PB_4"))
    )
    (comp (ref "U1")
      (value "TLP187")
      (footprint "LC-SOP-4_P2.54")
      (description "光藕")
      (libsource (lib "AirPlaneSign") (part "TLP187"))
    )
    (comp (ref "U2")
      (value "TLP187")
      (footprint "LC-SOP-4_P2.54")
      (description "光藕")
      (libsource (lib "AirPlaneSign") (part "TLP187"))
    )
    (comp (ref "U3")
      (value "TLP187")
      (footprint "LC-SOP-4_P2.54")
      (description "光藕")
      (libsource (lib "AirPlaneSign") (part "TLP187"))
    )
    (comp (ref "U4")
      (value "CAT6219-330TD-GT3")
      (footprint "SOT23-5")
      (description "CAT6219")
      (libsource (lib "My_Library") (part "CAT6219"))
    )
    (comp (ref "U5") (value "M-KL9") (footprint "M-KL9") (libsource (lib "AirPlaneSign") (part "M-KL9")))
    (comp (ref "U6")
      (value "TLP187")
      (footprint "LC-SOP-4_P2.54")
      (description "光藕")
      (libsource (lib "AirPlaneSign") (part "TLP187"))
    )
    (comp (ref "U7")
      (value "TLP187")
      (footprint "TLP187 - duplicate")
      (description "光藕")
      (libsource (lib "ControllerBoard") (part "Q817"))
    )
    (comp (ref "U8")
      (value "74HC04D")
      (footprint "SOIC-14_150mil")
      (description "6路施密特触发反相器")
      (fields (field (name "PUBLISHER") "Altium Limited"))
      (libsource (lib "AirPlaneSign") (part "74HC14"))
    )
    (comp (ref "U9")
      (value "MAX485ESA")
      (footprint "SOP-8_150mil")
      (description "RS485收发芯片")
      (libsource (lib "AirPlaneSign") (part "MAX485ESA"))
    )
    (comp (ref "U10")
      (value "RS485模块")
      (footprint "RS485MOD")
      (libsource (lib "AirPlaneSign") (part "RS485模块"))
    )
    (comp (ref "U11")
      (value "TLP187")
      (footprint "TLP187 - duplicate")
      (description "光藕")
      (libsource (lib "ControllerBoard") (part "Q817"))
    )
    (comp (ref "U12")
      (value "STM32F103RCT6")
      (footprint "LQFP-64_10x10x05P")
      (description "单片机")
      (libsource (lib "AirPlaneSign") (part "STM32F103RCT6"))
    )
    (comp (ref "U13")
      (value "立式micro 5p USB插座")
      (footprint "USB插座 micro 5p")
      (libsource (lib "AirPlaneSign") (part "USB_micro_5p"))
    )
    (comp (ref "V1")
      (value "S8050")
      (footprint "SOT-23-3")
      (description "NPN三极管")
      (fields (field (name "PUBLISHER") "Altium Limited"))
      (libsource (lib "AirPlaneSign") (part "NPN"))
    )
    (comp (ref "V2")
      (value "S8050")
      (footprint "SOT-23-3")
      (description "NPN三极管")
      (fields (field (name "PUBLISHER") "Altium Limited"))
      (libsource (lib "AirPlaneSign") (part "NPN"))
    )
    (comp (ref "XS1")
      (value "2Pin 2.54")
      (footprint "JXT-2")
      (description "单排插针")
      (fields (field (name "PUBLISHER") "Altium Limited"))
      (libsource (lib "My_Library") (part "Header 2H"))
    )
    (comp (ref "XS2")
      (value "2Pin 2.54")
      (footprint "JXT-2")
      (description "单排插针")
      (fields (field (name "PUBLISHER") "Altium Limited"))
      (libsource (lib "My_Library") (part "Header 2H"))
    )
    (comp (ref "XS3")
      (value "2Pin 2.54")
      (footprint "JXT-2")
      (description "单排插针")
      (fields (field (name "PUBLISHER") "Altium Limited"))
      (libsource (lib "My_Library") (part "Header 2H"))
    )
    (comp (ref "XS4")
      (value "2Pin 2.54")
      (footprint "JXT-2")
      (description "单排插针")
      (fields (field (name "PUBLISHER") "Altium Limited"))
      (libsource (lib "AirPlaneSign") (part "Header 2H"))
    )
    (comp (ref "XS5")
      (value "1.27 4PIN")
      (footprint "JXT-4")
      (description "1.27卧式贴片针座")
      (fields (field (name "PUBLISHER") "Altium Limited"))
      (libsource (lib "Miscellaneous Connectors") (part "Header 4"))
    )
    (comp (ref "XS6")
      (value "Header 2.54X4")
      (footprint "JXT-5")
      (description "1.27卧式贴片针座")
      (fields (field (name "PUBLISHER") "Altium Limited"))
      (libsource (lib "AirPlaneSign") (part "Header 5"))
    )
    (comp (ref "Y1")
      (value "32.768k")
      (footprint "3215_32.768K")
      (description "Crystal")
      (libsource (lib "Device Library") (part "CRYSTAL"))
    )
    (comp (ref "Y2")
      (value "8MHz ±20ppm 20pF")
      (footprint "LC-SMD-5032_4P")
      (description "贴片晶振")
      (libsource (lib "AirPlaneSign") (part "SMD-5032_4P 8MHz 20ppm 20pF"))
    )
  )
  (nets
    (net (code "1") (name "/1Y") (class "Default")
      (node (ref "R42") (pin "2") (pinfunction "2_2") (pintype "passive"))
      (node (ref "U8") (pin "11") (pinfunction "5Y_11") (pintype "passive"))
      (node (ref "U8") (pin "2") (pinfunction "1Y_2") (pintype "passive"))
    )
    (net (code "2") (name "/2A") (class "Default")
      (node (ref "U8") (pin "3") (pinfunction "2A_3") (pintype "passive"))
      (node (ref "U8") (pin "8") (pinfunction "4A_8") (pintype "passive"))
    )
    (net (code "3") (name "/485RX") (class "Default")
      (node (ref "U10") (pin "3") (pinfunction "RXD_3") (pintype "passive"))
      (node (ref "U12") (pin "17") (pinfunction "PA3/USART2_RX_/ADC12_IN3/TIM2_CH4_17") (pintype "passive"))
      (node (ref "U8") (pin "4") (pinfunction "2Y_4") (pintype "passive"))
      (node (ref "U8") (pin "5") (pinfunction "3A_5") (pintype "passive"))
    )
    (net (code "4") (name "/485TX") (class "Default")
      (node (ref "R39") (pin "1") (pinfunction "1_1") (pintype "passive"))
      (node (ref "U10") (pin "2") (pinfunction "TXD_2") (pintype "passive"))
      (node (ref "U12") (pin "16") (pinfunction "PA2/USART2_TX/ADC12_IN2/TIM2_CH3_16") (pintype "passive"))
      (node (ref "U8") (pin "1") (pinfunction "1A_1") (pintype "passive"))
    )
    (net (code "5") (name "/A") (class "Default")
      (node (ref "F3") (pin "2") (pinfunction "2_2") (pintype "passive"))
      (node (ref "P2") (pin "4") (pinfunction "4_4") (pintype "passive"))
      (node (ref "P2") (pin "6") (pinfunction "6_6") (pintype "passive"))
      (node (ref "R44") (pin "1") (pinfunction "1_1") (pintype "passive"))
      (node (ref "U10") (pin "7") (pinfunction "A+_7") (pintype "passive"))
    )
    (net (code "6") (name "/AIN1") (class "Default")
      (node (ref "Q1") (pin "3") (pinfunction "C/A_3") (pintype "power_in"))
      (node (ref "R22") (pin "2") (pinfunction "2_2") (pintype "passive"))
      (node (ref "U12") (pin "14") (pinfunction "PA0/WKUP/USART2_CTS/ADC12_IN0_/TIM2_CH1_ETR_14") (pintype "passive"))
    )
    (net (code "7") (name "/ANI2") (class "Default")
      (node (ref "Q3") (pin "3") (pinfunction "C/A_3") (pintype "power_in"))
      (node (ref "R34") (pin "2") (pinfunction "2_2") (pintype "passive"))
      (node (ref "U12") (pin "15") (pinfunction "PA1/USART2_RTS_/ADC12_IN1/TIM2_CH2_15") (pintype "passive"))
    )
    (net (code "8") (name "/AO-1") (class "Default")
      (node (ref "IC1") (pin "7") (pinfunction "2Out_7") (pintype "passive"))
      (node (ref "P2") (pin "17") (pinfunction "17_17") (pintype "passive"))
      (node (ref "R3") (pin "2") (pinfunction "2_2") (pintype "passive"))
    )
    (net (code "9") (name "/AO-2") (class "Default")
      (node (ref "IC1") (pin "1") (pinfunction "1Out_1") (pintype "passive"))
      (node (ref "P2") (pin "16") (pinfunction "16_16") (pintype "passive"))
      (node (ref "R2") (pin "2") (pinfunction "2_2") (pintype "passive"))
    )
    (net (code "10") (name "/AO1") (class "Default")
      (node (ref "R7") (pin "1") (pinfunction "1_1") (pintype "passive"))
      (node (ref "U12") (pin "10") (pinfunction "PC2/ADC12_IN12_10") (pintype "passive"))
    )
    (net (code "11") (name "/AO2") (class "Default")
      (node (ref "R14") (pin "1") (pinfunction "1_1") (pintype "passive"))
      (node (ref "U12") (pin "11") (pinfunction "PC3/ADC12_IN13_11") (pintype "passive"))
    )
    (net (code "12") (name "/AT_CMD") (class "Default")
      (node (ref "U12") (pin "55") (pinfunction "PB3/JTDO/TRACESWO/TIM2_CH2/SPI1_SCK_55") (pintype "passive"))
      (node (ref "U5") (pin "4") (pinfunction "AT_4") (pintype "passive"))
    )
    (net (code "13") (name "/B") (class "Default")
      (node (ref "F2") (pin "2") (pinfunction "2_2") (pintype "passive"))
      (node (ref "P2") (pin "3") (pinfunction "3_3") (pintype "passive"))
      (node (ref "P2") (pin "5") (pinfunction "5_5") (pintype "passive"))
      (node (ref "R44") (pin "2") (pinfunction "2_2") (pintype "passive"))
      (node (ref "U10") (pin "6") (pinfunction "B-_6") (pintype "passive"))
    )
    (net (code "14") (name "/BOOT0") (class "Default")
      (node (ref "R63") (pin "2") (pinfunction "2_2") (pintype "passive"))
      (node (ref "U12") (pin "60") (pinfunction "BOOT0_60") (pintype "passive"))
    )
    (net (code "15") (name "/BOOT1") (class "Default")
      (node (ref "R62") (pin "1") (pinfunction "1_1") (pintype "passive"))
      (node (ref "U12") (pin "28") (pinfunction "PB2-BOOT1_28") (pintype "passive"))
    )
    (net (code "16") (name "/D+") (class "Default")
      (node (ref "R59") (pin "1") (pinfunction "1_1") (pintype "passive"))
      (node (ref "R60") (pin "1") (pinfunction "1_1") (pintype "passive"))
      (node (ref "U13") (pin "3") (pinfunction "3_3") (pintype "passive"))
    )
    (net (code "17") (name "/D-") (class "Default")
      (node (ref "R57") (pin "1") (pinfunction "1_1") (pintype "passive"))
      (node (ref "U13") (pin "2") (pinfunction "2_2") (pintype "passive"))
    )
    (net (code "18") (name "/DC_IN") (class "Default")
      (node (ref "F1") (pin "1") (pinfunction "1_1") (pintype "passive"))
      (node (ref "P2") (pin "13") (pinfunction "13_13") (pintype "passive"))
    )
    (net (code "19") (name "/DI1") (class "Default")
      (node (ref "R19") (pin "2") (pinfunction "2_2") (pintype "passive"))
      (node (ref "U12") (pin "22") (pinfunction "PA6/SPI1_MISO_/TIM1_BKIN/ADC12_IN6/TIM3_CH1_22") (pintype "passive"))
      (node (ref "U3") (pin "3") (pinfunction "Emitter_3") (pintype "passive"))
    )
    (net (code "20") (name "/DI2") (class "Default")
      (node (ref "R33") (pin "2") (pinfunction "2_2") (pintype "passive"))
      (node (ref "U12") (pin "23") (pinfunction "PA7/SPI1_MISI_/TIM1_CH1N/ADC12_IN7/TIM3_CH2_23") (pintype "passive"))
      (node (ref "U6") (pin "3") (pinfunction "Emitter_3") (pintype "passive"))
    )
    (net (code "21") (name "/DI_1") (class "Default")
      (node (ref "P2") (pin "7") (pinfunction "7_7") (pintype "passive"))
      (node (ref "R15") (pin "1") (pinfunction "1_1") (pintype "passive"))
    )
    (net (code "22") (name "/DI_2") (class "Default")
      (node (ref "P2") (pin "8") (pinfunction "8_8") (pintype "passive"))
      (node (ref "R26") (pin "1") (pinfunction "1_1") (pintype "passive"))
    )
    (net (code "23") (name "/DO1") (class "Default")
      (node (ref "R1") (pin "1") (pinfunction "1_1") (pintype "passive"))
      (node (ref "U12") (pin "24") (pinfunction "PC4/ADC12_IN14_24") (pintype "passive"))
    )
    (net (code "24") (name "/DO2") (class "Default")
      (node (ref "R10") (pin "1") (pinfunction "1_1") (pintype "passive"))
      (node (ref "U12") (pin "25") (pinfunction "PC5/ADC12_IN15_25") (pintype "passive"))
    )
    (net (code "25") (name "/DO_1") (class "Default")
      (node (ref "P2") (pin "9") (pinfunction "9_9") (pintype "passive"))
      (node (ref "U1") (pin "3") (pinfunction "Emitter_3") (pintype "passive"))
    )
    (net (code "26") (name "/DO_2") (class "Default")
      (node (ref "P2") (pin "10") (pinfunction "10_10") (pintype "passive"))
      (node (ref "U2") (pin "3") (pinfunction "Emitter_3") (pintype "passive"))
    )
    (net (code "27") (name "/EPROM_SCL") (class "Default")
      (node (ref "AT1") (pin "6") (pinfunction "SCL_6") (pintype "passive"))
      (node (ref "R65") (pin "1") (pinfunction "1_1") (pintype "passive"))
      (node (ref "U12") (pin "58") (pinfunction "PB6/USART1_TX/I2C1_SCL_/TIM4_CH1_58") (pintype "passive"))
    )
    (net (code "28") (name "/EPROM_SDA") (class "Default")
      (node (ref "AT1") (pin "5") (pinfunction "SDA_5") (pintype "passive"))
      (node (ref "R66") (pin "1") (pinfunction "1_1") (pintype "passive"))
      (node (ref "U12") (pin "59") (pinfunction "PB7/USART1_RX/I2C1_SDA_/TIM4_CH2_59") (pintype "passive"))
    )
    (net (code "29") (name "/IIN1") (class "Default")
      (node (ref "C13") (pin "2") (pinfunction "2_2") (pintype "passive"))
      (node (ref "P2") (pin "14") (pinfunction "14_14") (pintype "passive"))
      (node (ref "R20") (pin "2") (pinfunction "2_2") (pintype "passive"))
      (node (ref "R22") (pin "1") (pinfunction "1_1") (pintype "passive"))
      (node (ref "R24") (pin "2") (pinfunction "2_2") (pintype "passive"))
    )
    (net (code "30") (name "/IIN2") (class "Default")
      (node (ref "C18") (pin "2") (pinfunction "2_2") (pintype "passive"))
      (node (ref "P2") (pin "1") (pinfunction "1_1") (pintype "passive"))
      (node (ref "R32") (pin "2") (pinfunction "2_2") (pintype "passive"))
      (node (ref "R34") (pin "1") (pinfunction "1_1") (pintype "passive"))
      (node (ref "R36") (pin "2") (pinfunction "2_2") (pintype "passive"))
    )
    (net (code "31") (name "/K1") (class "Default")
      (node (ref "R67") (pin "2") (pinfunction "2_2") (pintype "passive"))
      (node (ref "S2") (pin "1") (pinfunction "1_1") (pintype "passive"))
      (node (ref "U12") (pin "8") (pinfunction "PC0/ADC12_IN10_8") (pintype "passive"))
    )
    (net (code "32") (name "/K2") (class "Default")
      (node (ref "R68") (pin "2") (pinfunction "2_2") (pintype "passive"))
      (node (ref "S3") (pin "1") (pinfunction "1_1") (pintype "passive"))
      (node (ref "U12") (pin "9") (pinfunction "PC1/ADC12_IN11_9") (pintype "passive"))
    )
    (net (code "33") (name "/KCZJ-1") (class "Default")
      (node (ref "U12") (pin "26") (pinfunction "PB0/ADC12_IN8/TIM3_CH3/TIM1_CH2N_26") (pintype "passive"))
      (node (ref "U7") (pin "2") (pinfunction "LED_Cathode_2") (pintype "passive"))
    )
    (net (code "34") (name "/KCZJ-2") (class "Default")
      (node (ref "U11") (pin "2") (pinfunction "LED_Cathode_2") (pintype "passive"))
      (node (ref "U12") (pin "27") (pinfunction "PB1/ADC12_IN9/TIM3_CH4/TIM1_CH3N_27") (pintype "passive"))
    )
    (net (code "35") (name "/LED1") (class "Default")
      (node (ref "R38") (pin "1") (pinfunction "1_1") (pintype "passive"))
      (node (ref "U12") (pin "40") (pinfunction "PC9/TIM3_CH4_40") (pintype "passive"))
    )
    (net (code "36") (name "/LED2") (class "Default")
      (node (ref "R50") (pin "2") (pinfunction "2_2") (pintype "passive"))
      (node (ref "U12") (pin "39") (pinfunction "PC8/TIM3_CH3_39") (pintype "passive"))
    )
    (net (code "37") (name "/LED3") (class "Default")
      (node (ref "R51") (pin "1") (pinfunction "1_1") (pintype "passive"))
      (node (ref "U12") (pin "38") (pinfunction "PC7/TIM3_CH2_38") (pintype "passive"))
    )
    (net (code "38") (name "/LED4") (class "Default")
      (node (ref "R54") (pin "2") (pinfunction "2_2") (pintype "passive"))
      (node (ref "U12") (pin "37") (pinfunction "PC6/TIM3_CH1_37") (pintype "passive"))
    )
    (net (code "39") (name "/LED_1") (class "Default")
      (node (ref "LED2") (pin "1") (pinfunction "A_1") (pintype "passive"))
      (node (ref "P3") (pin "3") (pinfunction "3_3") (pintype "passive"))
      (node (ref "Q5") (pin "2") (pinfunction "E_2") (pintype "passive"))
    )
    (net (code "40") (name "/LED_2") (class "Default")
      (node (ref "LED2") (pin "3") (pinfunction "A_3") (pintype "passive"))
      (node (ref "P3") (pin "1") (pinfunction "1_1") (pintype "passive"))
      (node (ref "Q6") (pin "2") (pinfunction "E_2") (pintype "passive"))
    )
    (net (code "41") (name "/LED_3") (class "Default")
      (node (ref "LED4") (pin "1") (pinfunction "A_1") (pintype "passive"))
      (node (ref "P4") (pin "3") (pinfunction "3_3") (pintype "passive"))
      (node (ref "Q7") (pin "2") (pinfunction "E_2") (pintype "passive"))
    )
    (net (code "42") (name "/LED_4") (class "Default")
      (node (ref "LED4") (pin "3") (pinfunction "A_3") (pintype "passive"))
      (node (ref "P4") (pin "1") (pinfunction "1_1") (pintype "passive"))
      (node (ref "Q8") (pin "2") (pinfunction "E_2") (pintype "passive"))
    )
    (net (code "43") (name "/LED_A") (class "Default")
      (node (ref "LED2") (pin "2") (pinfunction "K_2") (pintype "passive"))
      (node (ref "P3") (pin "2") (pinfunction "2_2") (pintype "passive"))
      (node (ref "R43") (pin "2") (pinfunction "2_2") (pintype "passive"))
    )
    (net (code "44") (name "/LED_B") (class "Default")
      (node (ref "LED4") (pin "2") (pinfunction "K_2") (pintype "passive"))
      (node (ref "P4") (pin "2") (pinfunction "2_2") (pintype "passive"))
      (node (ref "R53") (pin "2") (pinfunction "2_2") (pintype "passive"))
    )
    (net (code "45") (name "/LORA_PWR") (class "Default")
      (node (ref "R31") (pin "1") (pinfunction "1_1") (pintype "passive"))
      (node (ref "U12") (pin "56") (pinfunction "PB4/JNTRST/TIM3_CH1/SPI1_MISO_56") (pintype "passive"))
    )
    (net (code "46") (name "/LoRa_RX") (class "Default")
      (node (ref "U12") (pin "29") (pinfunction "PB10/I2C2_SCL/USART3_TX/TIM2_CH3_29") (pintype "passive"))
      (node (ref "U5") (pin "5") (pinfunction "UART_RxD_5") (pintype "passive"))
    )
    (net (code "47") (name "/LoRa_TX") (class "Default")
      (node (ref "U12") (pin "30") (pinfunction "PB11/I2C2_SDA/USART3_RX/TIM2_CH4_30") (pintype "passive"))
      (node (ref "U5") (pin "6") (pinfunction "UART_TxD_6") (pintype "passive"))
    )
    (net (code "48") (name "/MCU_RX") (class "Default")
      (node (ref "U12") (pin "43") (pinfunction "PA10/USART1_RX/TIM1_CH3_43") (pintype "passive"))
      (node (ref "XS5") (pin "2") (pinfunction "2_2") (pintype "passive"))
    )
    (net (code "49") (name "/MCU_TX") (class "Default")
      (node (ref "U12") (pin "42") (pinfunction "PA9/USART1_TX/TIM1_CH2_42") (pintype "passive"))
      (node (ref "XS5") (pin "3") (pinfunction "3_3") (pintype "passive"))
    )
    (net (code "50") (name "/Power") (class "Default")
      (node (ref "LED1") (pin "1") (pinfunction "1_1") (pintype "passive"))
      (node (ref "R9") (pin "2") (pinfunction "2_2") (pintype "passive"))
      (node (ref "XS1") (pin "2") (pinfunction "2_2") (pintype "passive"))
    )
    (net (code "51") (name "/RESET") (class "Default")
      (node (ref "C32") (pin "1") (pinfunction "1_1") (pintype "passive"))
      (node (ref "R58") (pin "1") (pinfunction "1_1") (pintype "passive"))
      (node (ref "S1") (pin "2") (pinfunction "2_2") (pintype "passive"))
      (node (ref "U12") (pin "7") (pinfunction "NRST_7") (pintype "passive"))
      (node (ref "XS6") (pin "2") (pinfunction "2_2") (pintype "passive"))
    )
    (net (code "52") (name "/RESETn") (class "Default")
      (node (ref "R30") (pin "2") (pinfunction "2_2") (pintype "passive"))
      (node (ref "U12") (pin "53") (pinfunction "PC12/USART3_CK_53") (pintype "passive"))
      (node (ref "U5") (pin "8") (pinfunction "RESETn_8") (pintype "passive"))
    )
    (net (code "53") (name "/SWCLK") (class "Default")
      (node (ref "U12") (pin "49") (pinfunction "PA14/JTCK-SWCLK_49") (pintype "passive"))
      (node (ref "XS6") (pin "4") (pinfunction "4_4") (pintype "passive"))
    )
    (net (code "54") (name "/SWDIO") (class "Default")
      (node (ref "U12") (pin "46") (pinfunction "PA13/JTMS-SWDIO_46") (pintype "passive"))
      (node (ref "XS6") (pin "3") (pinfunction "3_3") (pintype "passive"))
    )
    (net (code "55") (name "/USBDM") (class "Default")
      (node (ref "R57") (pin "2") (pinfunction "2_2") (pintype "passive"))
      (node (ref "U12") (pin "44") (pinfunction "PA11/USART1_CTS/USBDM_/CAN_RX_/TIM1_CH4_44") (pintype "passive"))
    )
    (net (code "56") (name "/USBDP") (class "Default")
      (node (ref "R59") (pin "2") (pinfunction "2_2") (pintype "passive"))
      (node (ref "U12") (pin "45") (pinfunction "PA12/USART1_RTS/USBDP/CAN_TX_/TIM1_ETR_45") (pintype "passive"))
    )
    (net (code "57") (name "/VIN1") (class "Default")
      (node (ref "P2") (pin "15") (pinfunction "15_15") (pintype "passive"))
      (node (ref "R20") (pin "1") (pinfunction "1_1") (pintype "passive"))
    )
    (net (code "58") (name "/VIN2") (class "Default")
      (node (ref "P2") (pin "2") (pinfunction "2_2") (pintype "passive"))
      (node (ref "R32") (pin "1") (pinfunction "1_1") (pintype "passive"))
    )
    (net (code "59") (name "/WP") (class "Default")
      (node (ref "AT1") (pin "7") (pinfunction "WP_7") (pintype "passive"))
      (node (ref "R64") (pin "1") (pinfunction "1_1") (pintype "passive"))
      (node (ref "U12") (pin "57") (pinfunction "PB5/TIM3_CH2/SPI1_MOSI_/_I2C1_SMBA_57") (pintype "passive"))
    )
    (net (code "60") (name "/Wake_UP") (class "Default")
      (node (ref "R28") (pin "2") (pinfunction "2_2") (pintype "passive"))
      (node (ref "U12") (pin "54") (pinfunction "PD2/TIM3_ETR_54") (pintype "passive"))
      (node (ref "U5") (pin "7") (pinfunction "Wake_UP_7") (pintype "passive"))
    )
    (net (code "61") (name "3.3V") (class "Default")
      (node (ref "AT1") (pin "8") (pinfunction "VCC_8") (pintype "passive"))
      (node (ref "C19") (pin "1") (pinfunction "1_1") (pintype "passive"))
      (node (ref "C24") (pin "1") (pinfunction "1_1") (pintype "passive"))
      (node (ref "C25") (pin "1") (pinfunction "1_1") (pintype "passive"))
      (node (ref "C26") (pin "1") (pinfunction "1_1") (pintype "passive"))
      (node (ref "C29") (pin "2") (pinfunction "2_2") (pintype "passive"))
      (node (ref "C34") (pin "2") (pinfunction "2_2") (pintype "passive"))
      (node (ref "C35") (pin "2") (pinfunction "2_2") (pintype "passive"))
      (node (ref "C36") (pin "2") (pinfunction "2_2") (pintype "passive"))
      (node (ref "C37") (pin "2") (pinfunction "2_2") (pintype "passive"))
      (node (ref "C38") (pin "2") (pinfunction "2_2") (pintype "passive"))
      (node (ref "C39") (pin "1") (pinfunction "1_1") (pintype "passive"))
      (node (ref "C40") (pin "1") (pinfunction "1_1") (pintype "passive"))
      (node (ref "P5") (pin "1") (pinfunction "1_1") (pintype "passive"))
      (node (ref "P5") (pin "2") (pinfunction "2_2") (pintype "passive"))
      (node (ref "Q1") (pin "2") (pinfunction "CATHODE_2") (pintype "passive"))
      (node (ref "Q3") (pin "2") (pinfunction "CATHODE_2") (pintype "passive"))
      (node (ref "R37") (pin "2") (pinfunction "2_2") (pintype "passive"))
      (node (ref "R39") (pin "2") (pinfunction "2_2") (pintype "passive"))
      (node (ref "R41") (pin "2") (pinfunction "2_2") (pintype "passive"))
      (node (ref "R48") (pin "1") (pinfunction "1_1") (pintype "passive"))
      (node (ref "R49") (pin "1") (pinfunction "1_1") (pintype "passive"))
      (node (ref "R52") (pin "2") (pinfunction "2_2") (pintype "passive"))
      (node (ref "R58") (pin "2") (pinfunction "2_2") (pintype "passive"))
      (node (ref "R60") (pin "2") (pinfunction "2_2") (pintype "passive"))
      (node (ref "R64") (pin "2") (pinfunction "2_2") (pintype "passive"))
      (node (ref "R65") (pin "2") (pinfunction "2_2") (pintype "passive"))
      (node (ref "R66") (pin "2") (pinfunction "2_2") (pintype "passive"))
      (node (ref "R67") (pin "1") (pinfunction "1_1") (pintype "passive"))
      (node (ref "R68") (pin "1") (pinfunction "1_1") (pintype "passive"))
      (node (ref "U10") (pin "1") (pinfunction "VCC_1") (pintype "passive"))
      (node (ref "U12") (pin "13") (pinfunction "VDDA_13") (pintype "passive"))
      (node (ref "U12") (pin "19") (pinfunction "VDD4_19") (pintype "passive"))
      (node (ref "U12") (pin "32") (pinfunction "VDD1_32") (pintype "passive"))
      (node (ref "U12") (pin "48") (pinfunction "VDD2_48") (pintype "passive"))
      (node (ref "U12") (pin "64") (pinfunction "VDD3_64") (pintype "passive"))
      (node (ref "U3") (pin "4") (pinfunction "Collector_4") (pintype "passive"))
      (node (ref "U6") (pin "4") (pinfunction "Collector_4") (pintype "passive"))
      (node (ref "U8") (pin "14") (pinfunction "VCC_14") (pintype "passive"))
      (node (ref "U9") (pin "8") (pinfunction "VCC_8") (pintype "power_in"))
      (node (ref "XS5") (pin "1") (pinfunction "1_1") (pintype "passive"))
      (node (ref "XS6") (pin "5") (pinfunction "5_5") (pintype "passive"))
    )
    (net (code "62") (name "24V") (class "Default")
      (node (ref "C4") (pin "1") (pinfunction "1_1") (pintype "passive"))
      (node (ref "LM1") (pin "1") (pinfunction "VIN_1") (pintype "passive"))
      (node (ref "P1") (pin "2") (pinfunction "2_2") (pintype "passive"))
      (node (ref "P2") (pin "22") (pinfunction "22_22") (pintype "passive"))
      (node (ref "P2") (pin "23") (pinfunction "23_23") (pintype "passive"))
      (node (ref "P2") (pin "24") (pinfunction "24_24") (pintype "passive"))
      (node (ref "P2") (pin "25") (pinfunction "25_25") (pintype "passive"))
      (node (ref "RL1") (pin "6") (pinfunction "6_6") (pintype "passive"))
      (node (ref "RL2") (pin "6") (pinfunction "6_6") (pintype "passive"))
      (node (ref "U1") (pin "4") (pinfunction "Collector_4") (pintype "passive"))
      (node (ref "U2") (pin "4") (pinfunction "Collector_4") (pintype "passive"))
    )
    (net (code "63") (name "COM+1") (class "Default")
      (node (ref "P2") (pin "11") (pinfunction "11_11") (pintype "passive"))
      (node (ref "RL1") (pin "3") (pinfunction "3_3") (pintype "passive"))
      (node (ref "RL1") (pin "4") (pinfunction "4_4") (pintype "passive"))
    )
    (net (code "64") (name "COM+2") (class "Default")
      (node (ref "P2") (pin "12") (pinfunction "12_12") (pintype "passive"))
      (node (ref "RL2") (pin "3") (pinfunction "3_3") (pintype "passive"))
      (node (ref "RL2") (pin "4") (pinfunction "4_4") (pintype "passive"))
    )
    (net (code "65") (name "GND") (class "Default")
      (node (ref "AT1") (pin "1") (pinfunction "A0_1") (pintype "passive"))
      (node (ref "AT1") (pin "2") (pinfunction "A1_2") (pintype "passive"))
      (node (ref "AT1") (pin "3") (pinfunction "A2_3") (pintype "passive"))
      (node (ref "AT1") (pin "4") (pinfunction "GND_4") (pintype "passive"))
      (node (ref "C1") (pin "1") (pinfunction "1_1") (pintype "passive"))
      (node (ref "C10") (pin "2") (pinfunction "2_2") (pintype "passive"))
      (node (ref "C11") (pin "1") (pinfunction "1_1") (pintype "passive"))
      (node (ref "C12") (pin "1") (pinfunction "1_1") (pintype "passive"))
      (node (ref "C13") (pin "1") (pinfunction "1_1") (pintype "passive"))
      (node (ref "C14") (pin "1") (pinfunction "1_1") (pintype "passive"))
      (node (ref "C15") (pin "1") (pinfunction "1_1") (pintype "passive"))
      (node (ref "C16") (pin "1") (pinfunction "1_1") (pintype "passive"))
      (node (ref "C17") (pin "1") (pinfunction "1_1") (pintype "passive"))
      (node (ref "C18") (pin "1") (pinfunction "1_1") (pintype "passive"))
      (node (ref "C19") (pin "2") (pinfunction "2_2") (pintype "passive"))
      (node (ref "C2") (pin "1") (pinfunction "1_1") (pintype "passive"))
      (node (ref "C20") (pin "2") (pinfunction "2_2") (pintype "passive"))
      (node (ref "C21") (pin "1") (pinfunction "1_1") (pintype "passive"))
      (node (ref "C22") (pin "1") (pinfunction "1_1") (pintype "passive"))
      (node (ref "C23") (pin "1") (pinfunction "1_1") (pintype "passive"))
      (node (ref "C24") (pin "2") (pinfunction "2_2") (pintype "passive"))
      (node (ref "C25") (pin "2") (pinfunction "2_2") (pintype "passive"))
      (node (ref "C26") (pin "2") (pinfunction "2_2") (pintype "passive"))
      (node (ref "C27") (pin "2") (pinfunction "2_2") (pintype "passive"))
      (node (ref "C28") (pin "2") (pinfunction "2_2") (pintype "passive"))
      (node (ref "C29") (pin "1") (pinfunction "1_1") (pintype "passive"))
      (node (ref "C3") (pin "2") (pinfunction "2_2") (pintype "passive"))
      (node (ref "C30") (pin "2") (pinfunction "2_2") (pintype "passive"))
      (node (ref "C31") (pin "2") (pinfunction "2_2") (pintype "passive"))
      (node (ref "C32") (pin "2") (pinfunction "2_2") (pintype "passive"))
      (node (ref "C33") (pin "1") (pinfunction "1_1") (pintype "passive"))
      (node (ref "C34") (pin "1") (pinfunction "1_1") (pintype "passive"))
      (node (ref "C35") (pin "1") (pinfunction "1_1") (pintype "passive"))
      (node (ref "C36") (pin "1") (pinfunction "1_1") (pintype "passive"))
      (node (ref "C37") (pin "1") (pinfunction "1_1") (pintype "passive"))
      (node (ref "C38") (pin "1") (pinfunction "1_1") (pintype "passive"))
      (node (ref "C39") (pin "2") (pinfunction "2_2") (pintype "passive"))
      (node (ref "C4") (pin "2") (pinfunction "2_2") (pintype "passive"))
      (node (ref "C40") (pin "2") (pinfunction "2_2") (pintype "passive"))
      (node (ref "C5") (pin "1") (pinfunction "1_1") (pintype "passive"))
      (node (ref "C6") (pin "1") (pinfunction "1_1") (pintype "passive"))
      (node (ref "C7") (pin "1") (pinfunction "1_1") (pintype "passive"))
      (node (ref "C8") (pin "1") (pinfunction "1_1") (pintype "passive"))
      (node (ref "C9") (pin "1") (pinfunction "1_1") (pintype "passive"))
      (node (ref "D1") (pin "1") (pinfunction "A_1") (pintype "passive"))
      (node (ref "D12") (pin "K") (pinfunction "K_K") (pintype "passive"))
      (node (ref "D13") (pin "K") (pinfunction "K_K") (pintype "passive"))
      (node (ref "D2") (pin "1") (pinfunction "A_1") (pintype "passive"))
      (node (ref "D3") (pin "1") (pinfunction "A_1") (pintype "passive"))
      (node (ref "D4") (pin "1") (pinfunction "A_1") (pintype "passive"))
      (node (ref "D5") (pin "K") (pinfunction "K_K") (pintype "passive"))
      (node (ref "D6") (pin "K") (pinfunction "K_K") (pintype "passive"))
      (node (ref "D7") (pin "1") (pinfunction "A_1") (pintype "passive"))
      (node (ref "GND-1") (pin "1") (pinfunction "1_1") (pintype "passive"))
      (node (ref "GND1") (pin "1") (pinfunction "1_1") (pintype "passive"))
      (node (ref "IC1") (pin "4") (pinfunction "GND_4") (pintype "passive"))
      (node (ref "IC2") (pin "2") (pinfunction "GND_2") (pintype "passive"))
      (node (ref "LED1") (pin "2") (pinfunction "2_2") (pintype "passive"))
      (node (ref "LM1") (pin "3") (pinfunction "GND_3") (pintype "passive"))
      (node (ref "LM1") (pin "5") (pinfunction "ON/OFF_5") (pintype "passive"))
      (node (ref "P2") (pin "18") (pinfunction "18_18") (pintype "passive"))
      (node (ref "P2") (pin "19") (pinfunction "19_19") (pintype "passive"))
      (node (ref "P2") (pin "20") (pinfunction "20_20") (pintype "passive"))
      (node (ref "P2") (pin "21") (pinfunction "21_21") (pintype "passive"))
      (node (ref "P5") (pin "5") (pinfunction "5_5") (pintype "passive"))
      (node (ref "P5") (pin "6") (pinfunction "6_6") (pintype "passive"))
      (node (ref "Q1") (pin "1") (pinfunction "ANODE_1") (pintype "passive"))
      (node (ref "Q3") (pin "1") (pinfunction "ANODE_1") (pintype "passive"))
      (node (ref "Q4") (pin "2") (pinfunction "E_2") (pintype "passive"))
      (node (ref "R16") (pin "1") (pinfunction "1_1") (pintype "passive"))
      (node (ref "R19") (pin "1") (pinfunction "1_1") (pintype "passive"))
      (node (ref "R24") (pin "1") (pinfunction "1_1") (pintype "passive"))
      (node (ref "R28") (pin "1") (pinfunction "1_1") (pintype "passive"))
      (node (ref "R29") (pin "1") (pinfunction "1_1") (pintype "passive"))
      (node (ref "R33") (pin "1") (pinfunction "1_1") (pintype "passive"))
      (node (ref "R35") (pin "1") (pinfunction "1_1") (pintype "passive"))
      (node (ref "R36") (pin "1") (pinfunction "1_1") (pintype "passive"))
      (node (ref "R40") (pin "1") (pinfunction "1_1") (pintype "passive"))
      (node (ref "R43") (pin "1") (pinfunction "1_1") (pintype "passive"))
      (node (ref "R53") (pin "1") (pinfunction "1_1") (pintype "passive"))
      (node (ref "R61") (pin "1") (pinfunction "1_1") (pintype "passive"))
      (node (ref "RL1") (pin "1") (pinfunction "1_1") (pintype "passive"))
      (node (ref "RL2") (pin "1") (pinfunction "1_1") (pintype "passive"))
      (node (ref "S1") (pin "1") (pinfunction "1_1") (pintype "passive"))
      (node (ref "S2") (pin "2") (pinfunction "2_2") (pintype "passive"))
      (node (ref "S3") (pin "2") (pinfunction "2_2") (pintype "passive"))
      (node (ref "U1") (pin "2") (pinfunction "LED_Cathode_2") (pintype "passive"))
      (node (ref "U10") (pin "4") (pinfunction "GND_4") (pintype "passive"))
      (node (ref "U11") (pin "3") (pinfunction "Emitter_3") (pintype "passive"))
      (node (ref "U12") (pin "12") (pinfunction "VSSA_12") (pintype "passive"))
      (node (ref "U12") (pin "18") (pinfunction "VSS4_18") (pintype "passive"))
      (node (ref "U12") (pin "31") (pinfunction "VSS1_31") (pintype "passive"))
      (node (ref "U12") (pin "47") (pinfunction "VSS2_47") (pintype "passive"))
      (node (ref "U12") (pin "63") (pinfunction "VSS3_63") (pintype "passive"))
      (node (ref "U13") (pin "4") (pinfunction "4_4") (pintype "passive"))
      (node (ref "U2") (pin "2") (pinfunction "LED_Cathode_2") (pintype "passive"))
      (node (ref "U3") (pin "2") (pinfunction "LED_Cathode_2") (pintype "passive"))
      (node (ref "U4") (pin "2") (pinfunction "GND_2") (pintype "passive"))
      (node (ref "U5") (pin "9") (pinfunction "GND_9") (pintype "passive"))
      (node (ref "U6") (pin "2") (pinfunction "LED_Cathode_2") (pintype "passive"))
      (node (ref "U7") (pin "3") (pinfunction "Emitter_3") (pintype "passive"))
      (node (ref "U8") (pin "7") (pinfunction "GND_7") (pintype "passive"))
      (node (ref "U9") (pin "5") (pinfunction "GND_5") (pintype "power_in"))
      (node (ref "V1") (pin "2") (pinfunction "E_2") (pintype "passive"))
      (node (ref "V2") (pin "2") (pinfunction "E_2") (pintype "passive"))
      (node (ref "XS1") (pin "1") (pinfunction "1_1") (pintype "passive"))
      (node (ref "XS4") (pin "1") (pinfunction "1_1") (pintype "passive"))
      (node (ref "XS5") (pin "4") (pinfunction "4_4") (pintype "passive"))
      (node (ref "XS6") (pin "1") (pinfunction "1_1") (pintype "passive"))
      (node (ref "Y2") (pin "2") (pinfunction "G_2") (pintype "passive"))
      (node (ref "Y2") (pin "4") (pinfunction "G_4") (pintype "passive"))
    )
    (net (code "66") (name "GROUND") (class "Default")
      (node (ref "D14") (pin "1") (pinfunction "A_1") (pintype "passive"))
      (node (ref "D8") (pin "2") (pinfunction "K_2") (pintype "passive"))
      (node (ref "U10") (pin "5") (pinfunction "G_5") (pintype "passive"))
    )
    (net (code "67") (name "LoRa_3V3") (class "Default")
      (node (ref "C16") (pin "2") (pinfunction "2_2") (pintype "passive"))
      (node (ref "C17") (pin "2") (pinfunction "2_2") (pintype "passive"))
      (node (ref "R18") (pin "2") (pinfunction "2_2") (pintype "passive"))
      (node (ref "R30") (pin "1") (pinfunction "1_1") (pintype "passive"))
      (node (ref "U5") (pin "10") (pinfunction "VCC_10") (pintype "passive"))
    )
    (net (code "68") (name "Net-(C1-Pad2)") (class "Default")
      (node (ref "C1") (pin "2") (pinfunction "2_2") (pintype "passive"))
      (node (ref "R5") (pin "1") (pinfunction "1_1") (pintype "passive"))
      (node (ref "R6") (pin "2") (pinfunction "2_2") (pintype "passive"))
    )
    (net (code "69") (name "Net-(C7-Pad2)") (class "Default")
      (node (ref "C7") (pin "2") (pinfunction "2_2") (pintype "passive"))
      (node (ref "R12") (pin "1") (pinfunction "1_1") (pintype "passive"))
      (node (ref "R13") (pin "2") (pinfunction "2_2") (pintype "passive"))
    )
    (net (code "70") (name "Net-(C33-Pad2)") (class "Default")
      (node (ref "C33") (pin "2") (pinfunction "2_2") (pintype "passive"))
      (node (ref "R61") (pin "2") (pinfunction "2_2") (pintype "passive"))
      (node (ref "U13") (pin "5") (pinfunction "5_5") (pintype "passive"))
    )
    (net (code "71") (name "Net-(D1-K)") (class "Default")
      (node (ref "D1") (pin "2") (pinfunction "K_2") (pintype "passive"))
      (node (ref "R1") (pin "2") (pinfunction "2_2") (pintype "passive"))
      (node (ref "U1") (pin "1") (pinfunction "LED_Anode_1") (pintype "passive"))
    )
    (net (code "72") (name "Net-(D2-K)") (class "Default")
      (node (ref "D2") (pin "2") (pinfunction "K_2") (pintype "passive"))
      (node (ref "L1") (pin "1") (pinfunction "1_1") (pintype "passive"))
      (node (ref "LM1") (pin "2") (pinfunction "OUTPUT_2") (pintype "passive"))
    )
    (net (code "73") (name "Net-(D3-K)") (class "Default")
      (node (ref "D3") (pin "2") (pinfunction "K_2") (pintype "passive"))
      (node (ref "R10") (pin "2") (pinfunction "2_2") (pintype "passive"))
      (node (ref "U2") (pin "1") (pinfunction "LED_Anode_1") (pintype "passive"))
    )
    (net (code "74") (name "Net-(D4-K)") (class "Default")
      (node (ref "C9") (pin "2") (pinfunction "2_2") (pintype "passive"))
      (node (ref "D4") (pin "2") (pinfunction "K_2") (pintype "passive"))
      (node (ref "R15") (pin "2") (pinfunction "2_2") (pintype "passive"))
      (node (ref "R16") (pin "2") (pinfunction "2_2") (pintype "passive"))
      (node (ref "U3") (pin "1") (pinfunction "LED_Anode_1") (pintype "passive"))
    )
    (net (code "75") (name "Net-(D5-PadA)") (class "Default")
      (node (ref "D5") (pin "A") (pinfunction "A_A") (pintype "passive"))
      (node (ref "R23") (pin "1") (pinfunction "1_1") (pintype "passive"))
    )
    (net (code "76") (name "Net-(D6-PadA)") (class "Default")
      (node (ref "D6") (pin "A") (pinfunction "A_A") (pintype "passive"))
      (node (ref "R25") (pin "1") (pinfunction "1_1") (pintype "passive"))
    )
    (net (code "77") (name "Net-(D7-K)") (class "Default")
      (node (ref "C15") (pin "2") (pinfunction "2_2") (pintype "passive"))
      (node (ref "D7") (pin "2") (pinfunction "K_2") (pintype "passive"))
      (node (ref "R26") (pin "2") (pinfunction "2_2") (pintype "passive"))
      (node (ref "R29") (pin "2") (pinfunction "2_2") (pintype "passive"))
      (node (ref "U6") (pin "1") (pinfunction "LED_Anode_1") (pintype "passive"))
    )
    (net (code "78") (name "Net-(D8-A)") (class "Default")
      (node (ref "D8") (pin "1") (pinfunction "A_1") (pintype "passive"))
      (node (ref "D9") (pin "1") (pinfunction "A_1") (pintype "passive"))
      (node (ref "F2") (pin "1") (pinfunction "1_1") (pintype "passive"))
      (node (ref "R40") (pin "2") (pinfunction "2_2") (pintype "passive"))
      (node (ref "U9") (pin "7") (pinfunction "B_7") (pintype "power_in"))
    )
    (net (code "79") (name "Net-(D10-A)") (class "Default")
      (node (ref "D10") (pin "1") (pinfunction "A_1") (pintype "passive"))
      (node (ref "LED3") (pin "2") (pinfunction "2_2") (pintype "passive"))
      (node (ref "RL1") (pin "5") (pinfunction "5_5") (pintype "passive"))
      (node (ref "U7") (pin "4") (pinfunction "Collector_4") (pintype "passive"))
      (node (ref "XS2") (pin "1") (pinfunction "1_1") (pintype "passive"))
    )
    (net (code "80") (name "Net-(D12-PadA)") (class "Default")
      (node (ref "D12") (pin "A") (pinfunction "A_A") (pintype "passive"))
      (node (ref "R42") (pin "1") (pinfunction "1_1") (pintype "passive"))
    )
    (net (code "81") (name "Net-(D13-PadA)") (class "Default")
      (node (ref "D13") (pin "A") (pinfunction "A_A") (pintype "passive"))
      (node (ref "R45") (pin "1") (pinfunction "1_1") (pintype "passive"))
    )
    (net (code "82") (name "Net-(D14-K)") (class "Default")
      (node (ref "D14") (pin "2") (pinfunction "K_2") (pintype "passive"))
      (node (ref "D9") (pin "2") (pinfunction "K_2") (pintype "passive"))
      (node (ref "F3") (pin "1") (pinfunction "1_1") (pintype "passive"))
      (node (ref "R49") (pin "2") (pinfunction "2_2") (pintype "passive"))
      (node (ref "U9") (pin "6") (pinfunction "A_6") (pintype "power_in"))
    )
    (net (code "83") (name "Net-(D15-A)") (class "Default")
      (node (ref "D15") (pin "1") (pinfunction "A_1") (pintype "passive"))
      (node (ref "LED5") (pin "2") (pinfunction "2_2") (pintype "passive"))
      (node (ref "RL2") (pin "5") (pinfunction "5_5") (pintype "passive"))
      (node (ref "U11") (pin "4") (pinfunction "Collector_4") (pintype "passive"))
      (node (ref "XS3") (pin "1") (pinfunction "1_1") (pintype "passive"))
    )
    (net (code "84") (name "Net-(F1-Pad2)") (class "Default")
      (node (ref "F1") (pin "2") (pinfunction "2_2") (pintype "passive"))
      (node (ref "P1") (pin "1") (pinfunction "1_1") (pintype "passive"))
    )
    (net (code "85") (name "Net-(F4-Pad1)") (class "Default")
      (node (ref "F4") (pin "1") (pinfunction "1_1") (pintype "passive"))
      (node (ref "U13") (pin "1") (pinfunction "1_1") (pintype "passive"))
    )
    (net (code "86") (name "Net-(IC1-1IN+)") (class "Default")
      (node (ref "C2") (pin "2") (pinfunction "2_2") (pintype "passive"))
      (node (ref "IC1") (pin "3") (pinfunction "1IN+_3") (pintype "passive"))
      (node (ref "R5") (pin "2") (pinfunction "2_2") (pintype "passive"))
    )
    (net (code "87") (name "Net-(IC1-1IN-)") (class "Default")
      (node (ref "IC1") (pin "2") (pinfunction "1IN-_2") (pintype "passive"))
      (node (ref "R2") (pin "1") (pinfunction "1_1") (pintype "passive"))
    )
    (net (code "88") (name "Net-(IC1-2IN+)") (class "Default")
      (node (ref "C8") (pin "2") (pinfunction "2_2") (pintype "passive"))
      (node (ref "IC1") (pin "5") (pinfunction "2IN+_5") (pintype "passive"))
      (node (ref "R12") (pin "2") (pinfunction "2_2") (pintype "passive"))
    )
    (net (code "89") (name "Net-(IC1-2IN-)") (class "Default")
      (node (ref "IC1") (pin "6") (pinfunction "2IN-_6") (pintype "passive"))
      (node (ref "R3") (pin "1") (pinfunction "1_1") (pintype "passive"))
    )
    (net (code "90") (name "Net-(IC2-BYP)") (class "Default")
      (node (ref "C23") (pin "2") (pinfunction "2_2") (pintype "passive"))
      (node (ref "IC2") (pin "4") (pinfunction "BYP_4") (pintype "passive"))
    )
    (net (code "91") (name "Net-(IC2-VOUT)") (class "Default")
      (node (ref "2") (pin "1") (pinfunction "1_1") (pintype "passive"))
      (node (ref "C21") (pin "2") (pinfunction "2_2") (pintype "passive"))
      (node (ref "IC2") (pin "5") (pinfunction "VOUT_5") (pintype "passive"))
      (node (ref "R41") (pin "1") (pinfunction "1_1") (pintype "passive"))
    )
    (net (code "92") (name "Net-(LED3-Pad1)") (class "Default")
      (node (ref "LED3") (pin "1") (pinfunction "1_1") (pintype "passive"))
      (node (ref "R47") (pin "2") (pinfunction "2_2") (pintype "passive"))
      (node (ref "XS2") (pin "2") (pinfunction "2_2") (pintype "passive"))
    )
    (net (code "93") (name "Net-(LED5-Pad1)") (class "Default")
      (node (ref "LED5") (pin "1") (pinfunction "1_1") (pintype "passive"))
      (node (ref "R56") (pin "2") (pinfunction "2_2") (pintype "passive"))
      (node (ref "XS3") (pin "2") (pinfunction "2_2") (pintype "passive"))
    )
    (net (code "94") (name "Net-(LM1-FEEDBACK)") (class "Default")
      (node (ref "1") (pin "1") (pinfunction "1_1") (pintype "passive"))
      (node (ref "C3") (pin "1") (pinfunction "1_1") (pintype "passive"))
      (node (ref "C5") (pin "2") (pinfunction "2_2") (pintype "passive"))
      (node (ref "C6") (pin "2") (pinfunction "2_2") (pintype "passive"))
      (node (ref "L1") (pin "2") (pinfunction "2_2") (pintype "passive"))
      (node (ref "LM1") (pin "4") (pinfunction "FEEDBACK_4") (pintype "passive"))
      (node (ref "R8") (pin "1") (pinfunction "1_1") (pintype "passive"))
    )
    (net (code "95") (name "Net-(P5-Pad3)") (class "Default")
      (node (ref "P5") (pin "3") (pinfunction "3_3") (pintype "passive"))
      (node (ref "R62") (pin "2") (pinfunction "2_2") (pintype "passive"))
    )
    (net (code "96") (name "Net-(P5-Pad4)") (class "Default")
      (node (ref "P5") (pin "4") (pinfunction "4_4") (pintype "passive"))
      (node (ref "R63") (pin "1") (pinfunction "1_1") (pintype "passive"))
    )
    (net (code "97") (name "Net-(Q2-D)") (class "Default")
      (node (ref "Q2") (pin "3") (pinfunction "D_3") (pintype "passive"))
      (node (ref "R17") (pin "1") (pinfunction "1_1") (pintype "passive"))
    )
    (net (code "98") (name "Net-(Q2-G)") (class "Default")
      (node (ref "Q2") (pin "1") (pinfunction "G_1") (pintype "passive"))
      (node (ref "Q4") (pin "3") (pinfunction "C_3") (pintype "passive"))
      (node (ref "R27") (pin "1") (pinfunction "1_1") (pintype "passive"))
    )
    (net (code "99") (name "Net-(Q4-B)") (class "Default")
      (node (ref "Q4") (pin "1") (pinfunction "B_1") (pintype "passive"))
      (node (ref "R31") (pin "2") (pinfunction "2_2") (pintype "passive"))
      (node (ref "R35") (pin "2") (pinfunction "2_2") (pintype "passive"))
    )
    (net (code "100") (name "Net-(Q5-B)") (class "Default")
      (node (ref "Q5") (pin "1") (pinfunction "B_1") (pintype "passive"))
      (node (ref "R38") (pin "2") (pinfunction "2_2") (pintype "passive"))
    )
    (net (code "101") (name "Net-(Q6-B)") (class "Default")
      (node (ref "Q6") (pin "1") (pinfunction "B_1") (pintype "passive"))
      (node (ref "R50") (pin "1") (pinfunction "1_1") (pintype "passive"))
    )
    (net (code "102") (name "Net-(Q7-B)") (class "Default")
      (node (ref "Q7") (pin "1") (pinfunction "B_1") (pintype "passive"))
      (node (ref "R51") (pin "2") (pinfunction "2_2") (pintype "passive"))
    )
    (net (code "103") (name "Net-(Q8-B)") (class "Default")
      (node (ref "Q8") (pin "1") (pinfunction "B_1") (pintype "passive"))
      (node (ref "R54") (pin "1") (pinfunction "1_1") (pintype "passive"))
    )
    (net (code "104") (name "Net-(R55-Pad1)") (class "Default")
      (node (ref "R55") (pin "1") (pinfunction "1_1") (pintype "passive"))
      (node (ref "XS4") (pin "2") (pinfunction "2_2") (pintype "passive"))
    )
    (net (code "105") (name "Net-(U4-BYP)") (class "Default")
      (node (ref "C12") (pin "2") (pinfunction "2_2") (pintype "passive"))
      (node (ref "U4") (pin "4") (pinfunction "BYP_4") (pintype "passive"))
    )
    (net (code "106") (name "Net-(U4-EN)") (class "Default")
      (node (ref "R21") (pin "2") (pinfunction "2_2") (pintype "passive"))
      (node (ref "U4") (pin "3") (pinfunction "EN_3") (pintype "passive"))
    )
    (net (code "107") (name "Net-(U4-VIN)") (class "Default")
      (node (ref "C10") (pin "1") (pinfunction "1_1") (pintype "passive"))
      (node (ref "C14") (pin "2") (pinfunction "2_2") (pintype "passive"))
      (node (ref "R17") (pin "2") (pinfunction "2_2") (pintype "passive"))
      (node (ref "R21") (pin "1") (pinfunction "1_1") (pintype "passive"))
      (node (ref "U4") (pin "1") (pinfunction "VIN_1") (pintype "passive"))
    )
    (net (code "108") (name "Net-(U4-VOUT)") (class "Default")
      (node (ref "C11") (pin "2") (pinfunction "2_2") (pintype "passive"))
      (node (ref "LoRa-1") (pin "1") (pinfunction "1_1") (pintype "passive"))
      (node (ref "R18") (pin "1") (pinfunction "1_1") (pintype "passive"))
      (node (ref "U4") (pin "5") (pinfunction "VOUT_5") (pintype "passive"))
    )
    (net (code "109") (name "Net-(U5-GPIO1)") (class "Default")
      (node (ref "R23") (pin "2") (pinfunction "2_2") (pintype "passive"))
      (node (ref "U5") (pin "1") (pinfunction "GPIO1_1") (pintype "passive"))
    )
    (net (code "110") (name "Net-(U5-GPIO2)") (class "Default")
      (node (ref "R25") (pin "2") (pinfunction "2_2") (pintype "passive"))
      (node (ref "U5") (pin "2") (pinfunction "GPIO2_2") (pintype "passive"))
    )
    (net (code "111") (name "Net-(U7-LED_Anode)") (class "Default")
      (node (ref "R37") (pin "1") (pinfunction "1_1") (pintype "passive"))
      (node (ref "U7") (pin "1") (pinfunction "LED_Anode_1") (pintype "passive"))
    )
    (net (code "112") (name "Net-(U8-3Y)") (class "Default")
      (node (ref "R45") (pin "2") (pinfunction "2_2") (pintype "passive"))
      (node (ref "U8") (pin "6") (pinfunction "3Y_6") (pintype "passive"))
    )
    (net (code "113") (name "Net-(U8-4Y)") (class "Default")
      (node (ref "R48") (pin "2") (pinfunction "2_2") (pintype "passive"))
      (node (ref "U8") (pin "9") (pinfunction "4Y_9") (pintype "passive"))
      (node (ref "U9") (pin "1") (pinfunction "RO_1") (pintype "power_in"))
    )
    (net (code "114") (name "Net-(U8-5A)") (class "Default")
      (node (ref "D11") (pin "2") (pinfunction "1_2") (pintype "passive"))
      (node (ref "R46") (pin "1") (pinfunction "1_1") (pintype "passive"))
      (node (ref "U8") (pin "10") (pinfunction "5A_10") (pintype "passive"))
      (node (ref "U9") (pin "4") (pinfunction "DI_4") (pintype "power_in"))
    )
    (net (code "115") (name "Net-(U8-6A)") (class "Default")
      (node (ref "U8") (pin "12") (pinfunction "6A_12") (pintype "passive"))
      (node (ref "U9") (pin "2") (pinfunction "~{RE}_2") (pintype "power_in"))
      (node (ref "U9") (pin "3") (pinfunction "DE_3") (pintype "power_in"))
    )
    (net (code "116") (name "Net-(U8-6Y)") (class "Default")
      (node (ref "C20") (pin "1") (pinfunction "1_1") (pintype "passive"))
      (node (ref "D11") (pin "1") (pinfunction "1_1") (pintype "passive"))
      (node (ref "R46") (pin "2") (pinfunction "2_2") (pintype "passive"))
      (node (ref "U8") (pin "13") (pinfunction "6Y_13") (pintype "passive"))
    )
    (net (code "117") (name "Net-(U11-LED_Anode)") (class "Default")
      (node (ref "R52") (pin "1") (pinfunction "1_1") (pintype "passive"))
      (node (ref "U11") (pin "1") (pinfunction "LED_Anode_1") (pintype "passive"))
    )
    (net (code "118") (name "Net-(U12-PC14{slash}OSC32_IN)") (class "Default")
      (node (ref "C28") (pin "1") (pinfunction "1_1") (pintype "passive"))
      (node (ref "U12") (pin "3") (pinfunction "PC14/OSC32_IN_3") (pintype "passive"))
      (node (ref "Y1") (pin "2") (pinfunction "2_2") (pintype "passive"))
    )
    (net (code "119") (name "Net-(U12-PC15{slash}OSC32_OUT)") (class "Default")
      (node (ref "C27") (pin "1") (pinfunction "1_1") (pintype "passive"))
      (node (ref "U12") (pin "4") (pinfunction "PC15/OSC32_OUT_4") (pintype "passive"))
      (node (ref "Y1") (pin "1") (pinfunction "1_1") (pintype "passive"))
    )
    (net (code "120") (name "Net-(U12-PD0{slash}OSC_IN)") (class "Default")
      (node (ref "C31") (pin "1") (pinfunction "1_1") (pintype "passive"))
      (node (ref "U12") (pin "5") (pinfunction "PD0/OSC_IN_5") (pintype "passive"))
      (node (ref "Y2") (pin "3") (pinfunction "T2_3") (pintype "passive"))
    )
    (net (code "121") (name "Net-(U12-PD1{slash}OSC_OUT)") (class "Default")
      (node (ref "C30") (pin "1") (pinfunction "1_1") (pintype "passive"))
      (node (ref "U12") (pin "6") (pinfunction "PD1/OSC_OUT_6") (pintype "passive"))
      (node (ref "Y2") (pin "1") (pinfunction "T1_1") (pintype "passive"))
    )
    (net (code "122") (name "Net-(V1-B)") (class "Default")
      (node (ref "R7") (pin "2") (pinfunction "2_2") (pintype "passive"))
      (node (ref "V1") (pin "1") (pinfunction "B_1") (pintype "passive"))
    )
    (net (code "123") (name "Net-(V1-C)") (class "Default")
      (node (ref "R4") (pin "1") (pinfunction "1_1") (pintype "passive"))
      (node (ref "R6") (pin "1") (pinfunction "1_1") (pintype "passive"))
      (node (ref "V1") (pin "3") (pinfunction "C_3") (pintype "passive"))
    )
    (net (code "124") (name "Net-(V2-B)") (class "Default")
      (node (ref "R14") (pin "2") (pinfunction "2_2") (pintype "passive"))
      (node (ref "V2") (pin "1") (pinfunction "B_1") (pintype "passive"))
    )
    (net (code "125") (name "Net-(V2-C)") (class "Default")
      (node (ref "R11") (pin "1") (pinfunction "1_1") (pintype "passive"))
      (node (ref "R13") (pin "1") (pinfunction "1_1") (pintype "passive"))
      (node (ref "V2") (pin "3") (pinfunction "C_3") (pintype "passive"))
    )
    (net (code "126") (name "VCC5V") (class "Default")
      (node (ref "C22") (pin "2") (pinfunction "2_2") (pintype "passive"))
      (node (ref "D10") (pin "2") (pinfunction "K_2") (pintype "passive"))
      (node (ref "D15") (pin "2") (pinfunction "K_2") (pintype "passive"))
      (node (ref "F4") (pin "2") (pinfunction "2_2") (pintype "passive"))
      (node (ref "IC1") (pin "8") (pinfunction "Vdd_8") (pintype "passive"))
      (node (ref "IC2") (pin "1") (pinfunction "VIN_1") (pintype "passive"))
      (node (ref "IC2") (pin "3") (pinfunction "EN_3") (pintype "passive"))
      (node (ref "Q2") (pin "2") (pinfunction "S_2") (pintype "passive"))
      (node (ref "Q5") (pin "3") (pinfunction "C_3") (pintype "passive"))
      (node (ref "Q6") (pin "3") (pinfunction "C_3") (pintype "passive"))
      (node (ref "Q7") (pin "3") (pinfunction "C_3") (pintype "passive"))
      (node (ref "Q8") (pin "3") (pinfunction "C_3") (pintype "passive"))
      (node (ref "R11") (pin "2") (pinfunction "2_2") (pintype "passive"))
      (node (ref "R27") (pin "2") (pinfunction "2_2") (pintype "passive"))
      (node (ref "R4") (pin "2") (pinfunction "2_2") (pintype "passive"))
      (node (ref "R47") (pin "1") (pinfunction "1_1") (pintype "passive"))
      (node (ref "R56") (pin "1") (pinfunction "1_1") (pintype "passive"))
      (node (ref "R8") (pin "2") (pinfunction "2_2") (pintype "passive"))
      (node (ref "R9") (pin "1") (pinfunction "1_1") (pintype "passive"))
      (node (ref "RL1") (pin "2") (pinfunction "2_2") (pintype "passive"))
      (node (ref "RL2") (pin "2") (pinfunction "2_2") (pintype "passive"))
    )
    (net (code "127") (name "VRTC") (class "Default")
      (node (ref "R55") (pin "2") (pinfunction "2_2") (pintype "passive"))
      (node (ref "U12") (pin "1") (pinfunction "VBAT_1") (pintype "passive"))
    )
    (net (code "128") (name "unconnected-(U5-ANT-Pad12)") (class "Default")
      (node (ref "U5") (pin "12") (pinfunction "ANT_12") (pintype "passive+no_connect"))
    )
    (net (code "129") (name "unconnected-(U5-CLK-Pad15)") (class "Default")
      (node (ref "U5") (pin "15") (pinfunction "CLK_15") (pintype "passive+no_connect"))
    )
    (net (code "130") (name "unconnected-(U5-DIO-Pad14)") (class "Default")
      (node (ref "U5") (pin "14") (pinfunction "DIO_14") (pintype "passive+no_connect"))
    )
    (net (code "131") (name "unconnected-(U5-GND-Pad11)") (class "Default")
      (node (ref "U5") (pin "11") (pinfunction "GND_11") (pintype "passive+no_connect"))
    )
    (net (code "132") (name "unconnected-(U5-GND-Pad13)") (class "Default")
      (node (ref "U5") (pin "13") (pinfunction "GND_13") (pintype "passive+no_connect"))
    )
    (net (code "133") (name "unconnected-(U5-GND-Pad16)") (class "Default")
      (node (ref "U5") (pin "16") (pinfunction "GND_16") (pintype "passive+no_connect"))
    )
    (net (code "134") (name "unconnected-(U5-GPIO3-Pad3)") (class "Default")
      (node (ref "U5") (pin "3") (pinfunction "GPIO3_3") (pintype "passive+no_connect"))
    )
    (net (code "135") (name "unconnected-(U12-PA4{slash}SPI1_NSS{slash}_USART2_CK{slash}ADC12_IN4-Pad20)") (class "Default")
      (node (ref "U12") (pin "20") (pinfunction "PA4/SPI1_NSS/_USART2_CK/ADC12_IN4_20") (pintype "passive+no_connect"))
    )
    (net (code "136") (name "unconnected-(U12-PA5{slash}SPI1_SCK_{slash}ADC12_IN5-Pad21)") (class "Default")
      (node (ref "U12") (pin "21") (pinfunction "PA5/SPI1_SCK_/ADC12_IN5_21") (pintype "passive+no_connect"))
    )
    (net (code "137") (name "unconnected-(U12-PA8{slash}USART1_CK{slash}TIM1_CH1{slash}MCO-Pad41)") (class "Default")
      (node (ref "U12") (pin "41") (pinfunction "PA8/USART1_CK/TIM1_CH1/MCO_41") (pintype "passive+no_connect"))
    )
    (net (code "138") (name "unconnected-(U12-PA15{slash}JTDI{slash}TIM2_CH1_CH1{slash}_SPI1_NSS-Pad50)") (class "Default")
      (node (ref "U12") (pin "50") (pinfunction "PA15/JTDI/TIM2_CH1_CH1/_SPI1_NSS_50") (pintype "passive+no_connect"))
    )
    (net (code "139") (name "unconnected-(U12-PB8{slash}I2C_1_SCL{slash}_CAN_RX{slash}TIM4_CH3-Pad61)") (class "Default")
      (node (ref "U12") (pin "61") (pinfunction "PB8/I2C_1_SCL/_CAN_RX/TIM4_CH3_61") (pintype "passive+no_connect"))
    )
    (net (code "140") (name "unconnected-(U12-PB9{slash}I2C_1_SDA{slash}CAN_TX{slash}TIM4_CH4-Pad62)") (class "Default")
      (node (ref "U12") (pin "62") (pinfunction "PB9/I2C_1_SDA/CAN_TX/TIM4_CH4_62") (pintype "passive+no_connect"))
    )
    (net (code "141") (name "unconnected-(U12-PB12{slash}SPI2_NSS{slash}I2C2_SMBA{slash}USART3_CK{slash}TIM1_BKIN-Pad33)") (class "Default")
      (node (ref "U12") (pin "33") (pinfunction "PB12/SPI2_NSS/I2C2_SMBA/USART3_CK/TIM1_BKIN_33") (pintype "passive"))
    )
    (net (code "142") (name "unconnected-(U12-PB13{slash}SPI2_SCK{slash}USART3_CTS{slash}_TIM1_CH1N-Pad34)") (class "Default")
      (node (ref "U12") (pin "34") (pinfunction "PB13/SPI2_SCK/USART3_CTS/_TIM1_CH1N_34") (pintype "passive"))
    )
    (net (code "143") (name "unconnected-(U12-PB14{slash}SPI2_MISO{slash}TIM1_CH2N{slash}USART3_RTS-Pad35)") (class "Default")
      (node (ref "U12") (pin "35") (pinfunction "PB14/SPI2_MISO/TIM1_CH2N/USART3_RTS_35") (pintype "passive"))
    )
    (net (code "144") (name "unconnected-(U12-PB15{slash}SPI2_MOSI{slash}TIM1_CH3N-Pad36)") (class "Default")
      (node (ref "U12") (pin "36") (pinfunction "PB15/SPI2_MOSI/TIM1_CH3N_36") (pintype "passive"))
    )
    (net (code "145") (name "unconnected-(U12-PC10{slash}USART3_TX-Pad51)") (class "Default")
      (node (ref "U12") (pin "51") (pinfunction "PC10/USART3_TX_51") (pintype "passive+no_connect"))
    )
    (net (code "146") (name "unconnected-(U12-PC11{slash}USART3_RX-Pad52)") (class "Default")
      (node (ref "U12") (pin "52") (pinfunction "PC11/USART3_RX_52") (pintype "passive+no_connect"))
    )
    (net (code "147") (name "unconnected-(U12-PC13{slash}TAMPER-RTC-Pad2)") (class "Default")
      (node (ref "U12") (pin "2") (pinfunction "PC13/TAMPER-RTC_2") (pintype "passive+no_connect"))
    )
  )
)
